# ZynqCoreBoard1.net
KiCad netlist of a schematic drawn in Altium Designer
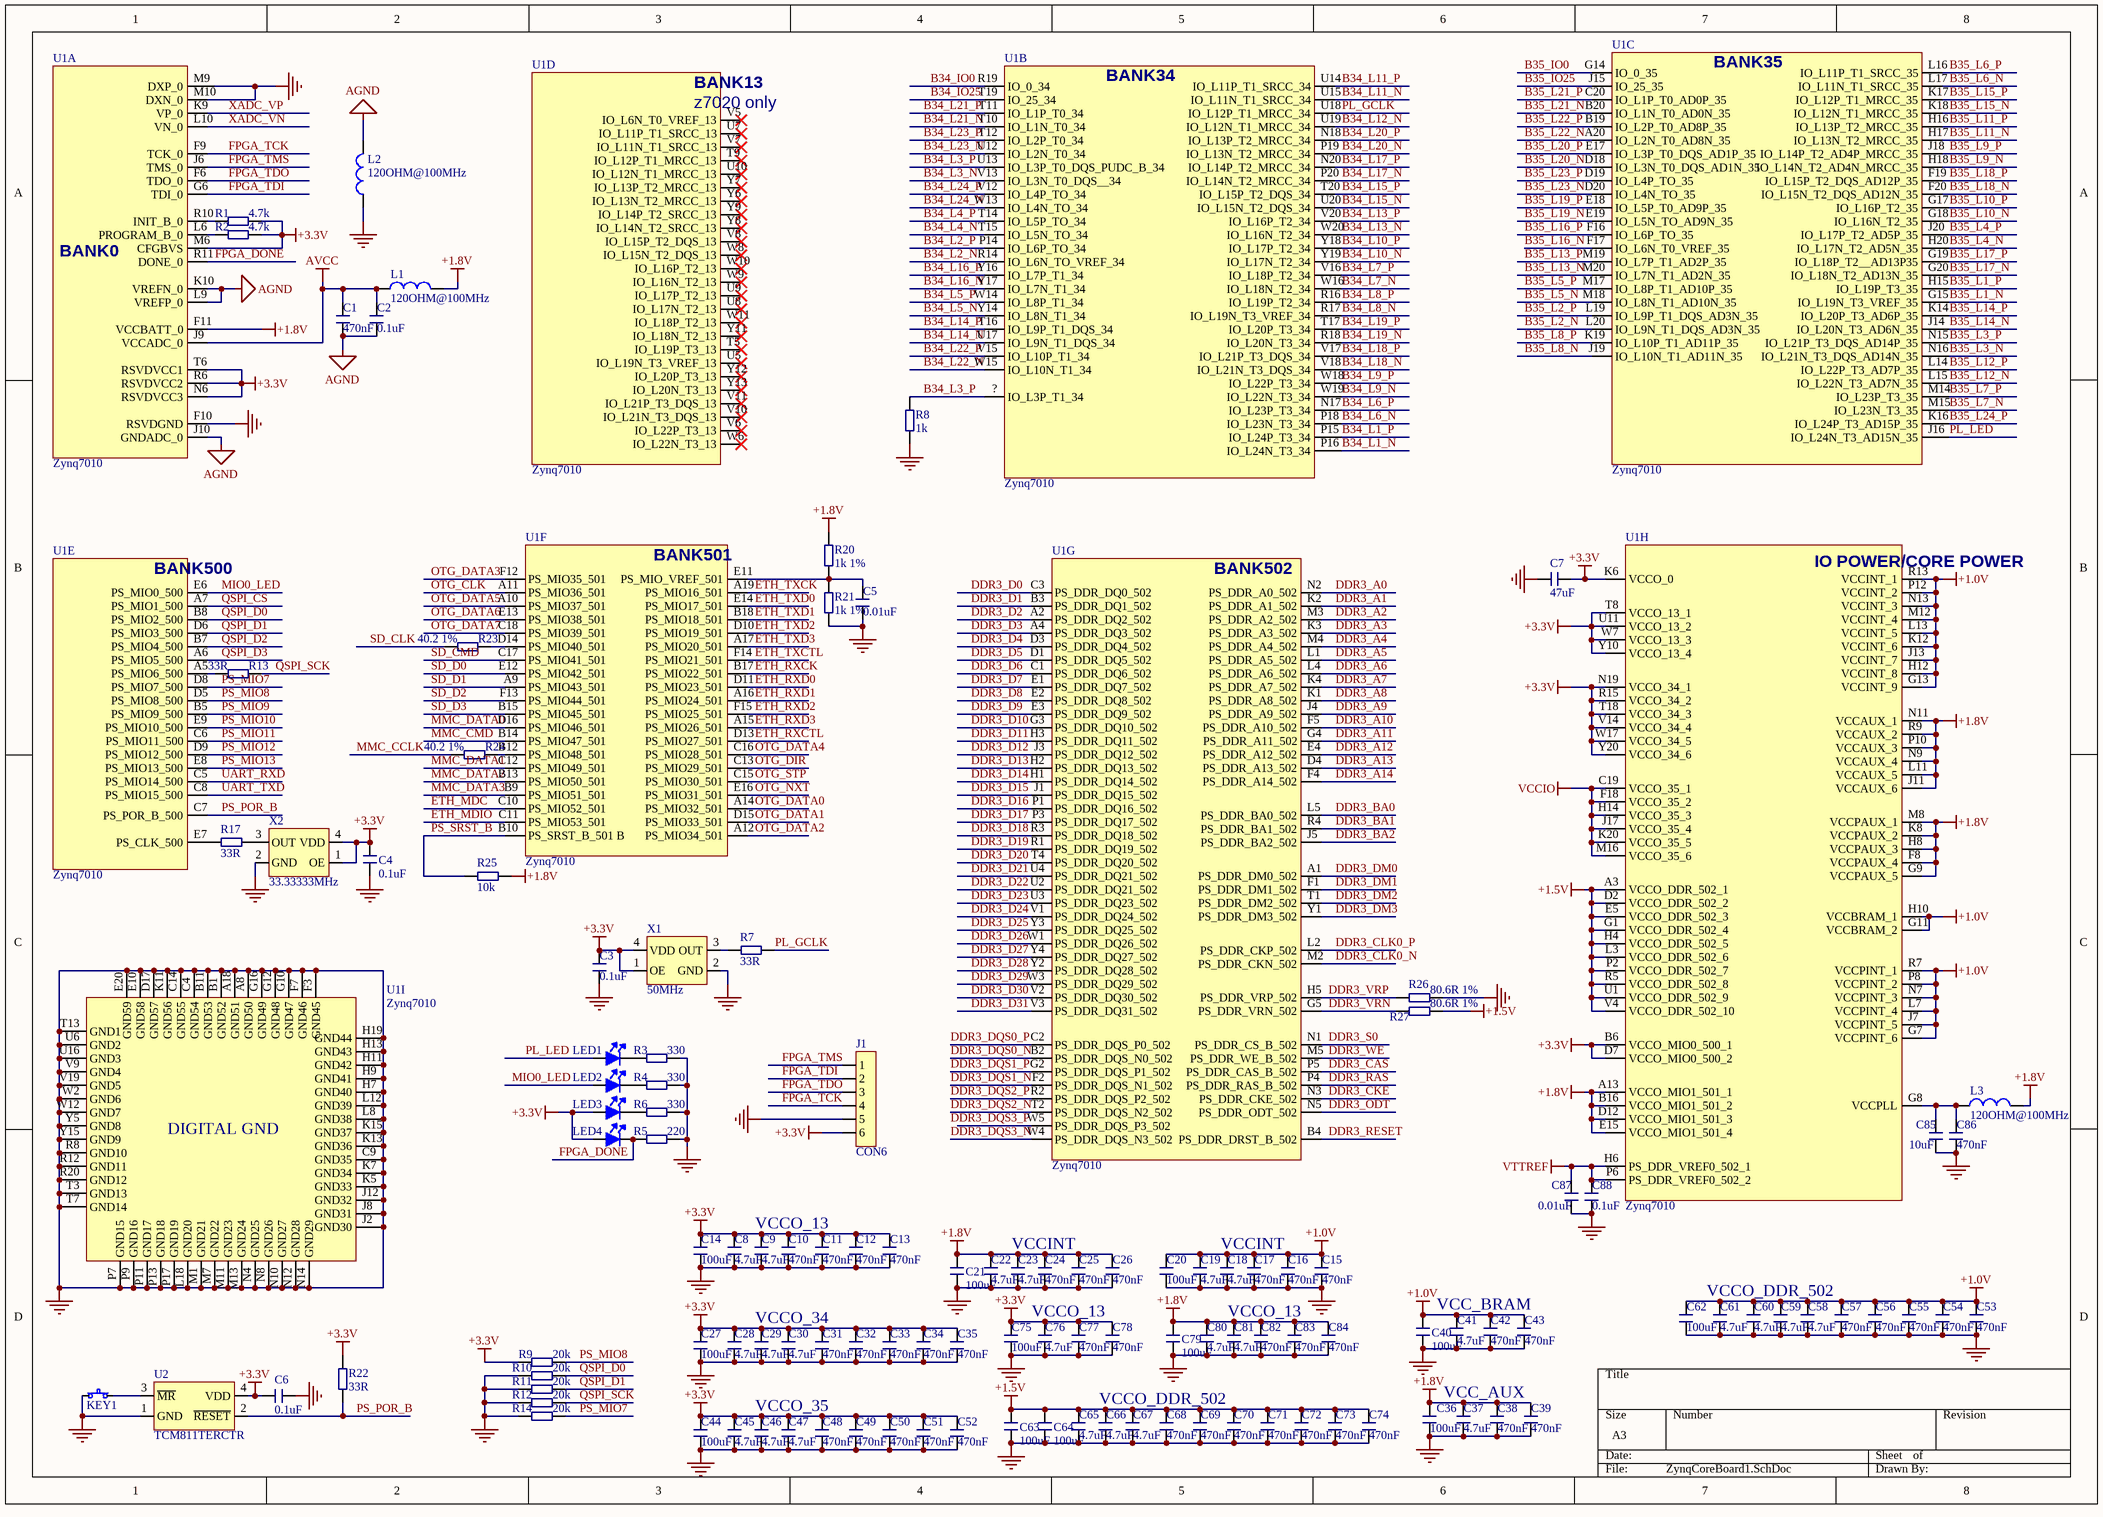
[diagram p0: ZynqCoreBoard1.SchDoc]

(export (version "E")
  (design (tool "Eeschema 10.0.6"))
  (components
    (comp (ref "C1")
      (value "470nF")
      (footprint "C0402")
      (libsource (lib "zynqCoreboard_SCHLIB") (part "C0402"))
    )
    (comp (ref "C2")
      (value "0.1uF")
      (footprint "C0402")
      (libsource (lib "zynqCoreboard_SCHLIB") (part "C0402"))
    )
    (comp (ref "C3")
      (value "0.1uF")
      (footprint "C0402")
      (libsource (lib "zynqCoreboard_SCHLIB") (part "C0402"))
    )
    (comp (ref "C4")
      (value "0.1uF")
      (footprint "C0402")
      (libsource (lib "zynqCoreboard_SCHLIB") (part "C0402"))
    )
    (comp (ref "C5")
      (value "0.01uF")
      (footprint "C0402")
      (libsource (lib "zynqCoreboard_SCHLIB") (part "C0402"))
    )
    (comp (ref "C6")
      (value "0.1uF")
      (footprint "C0402")
      (libsource (lib "zynqCoreboard_SCHLIB") (part "C0402"))
    )
    (comp (ref "C7")
      (value "47uF")
      (footprint "C0603")
      (libsource (lib "zynqCoreboard_SCHLIB") (part "C0603"))
    )
    (comp (ref "C8")
      (value "4.7uF")
      (footprint "C0402")
      (libsource (lib "zynqCoreboard_SCHLIB") (part "C0402"))
    )
    (comp (ref "C9")
      (value "4.7uF")
      (footprint "C0402")
      (libsource (lib "zynqCoreboard_SCHLIB") (part "C0402"))
    )
    (comp (ref "C10")
      (value "470nF")
      (footprint "C0402")
      (libsource (lib "zynqCoreboard_SCHLIB") (part "C0402"))
    )
    (comp (ref "C11")
      (value "470nF")
      (footprint "C0402")
      (libsource (lib "zynqCoreboard_SCHLIB") (part "C0402"))
    )
    (comp (ref "C12")
      (value "470nF")
      (footprint "C0402")
      (libsource (lib "zynqCoreboard_SCHLIB") (part "C0402"))
    )
    (comp (ref "C13")
      (value "470nF")
      (footprint "C0402")
      (libsource (lib "zynqCoreboard_SCHLIB") (part "C0402"))
    )
    (comp (ref "C14")
      (value "100uF")
      (footprint "C1206")
      (libsource (lib "zynqCoreboard_SCHLIB") (part "C_3528B"))
    )
    (comp (ref "C15")
      (value "470nF")
      (footprint "C0402")
      (libsource (lib "zynqCoreboard_SCHLIB") (part "C0402"))
    )
    (comp (ref "C16")
      (value "470nF")
      (footprint "C0402")
      (libsource (lib "zynqCoreboard_SCHLIB") (part "C0402"))
    )
    (comp (ref "C17")
      (value "470nF")
      (footprint "C0402")
      (libsource (lib "zynqCoreboard_SCHLIB") (part "C0402"))
    )
    (comp (ref "C18")
      (value "4.7uF")
      (footprint "C0402")
      (libsource (lib "zynqCoreboard_SCHLIB") (part "C0402"))
    )
    (comp (ref "C19")
      (value "4.7uF")
      (footprint "C0402")
      (libsource (lib "zynqCoreboard_SCHLIB") (part "C0402"))
    )
    (comp (ref "C20")
      (value "100uF")
      (footprint "C1206")
      (libsource (lib "zynqCoreboard_SCHLIB") (part "C_3528B"))
    )
    (comp (ref "C21")
      (value "100uF")
      (footprint "C1206")
      (libsource (lib "zynqCoreboard_SCHLIB") (part "C_3528B"))
    )
    (comp (ref "C22")
      (value "4.7uF")
      (footprint "C0402")
      (libsource (lib "zynqCoreboard_SCHLIB") (part "C0402"))
    )
    (comp (ref "C23")
      (value "4.7uF")
      (footprint "C0402")
      (libsource (lib "zynqCoreboard_SCHLIB") (part "C0402"))
    )
    (comp (ref "C24")
      (value "470nF")
      (footprint "C0402")
      (libsource (lib "zynqCoreboard_SCHLIB") (part "C0402"))
    )
    (comp (ref "C25")
      (value "470nF")
      (footprint "C0402")
      (libsource (lib "zynqCoreboard_SCHLIB") (part "C0402"))
    )
    (comp (ref "C26")
      (value "470nF")
      (footprint "C0402")
      (libsource (lib "zynqCoreboard_SCHLIB") (part "C0402"))
    )
    (comp (ref "C27")
      (value "100uF")
      (footprint "C1206")
      (libsource (lib "zynqCoreboard_SCHLIB") (part "C_3528B"))
    )
    (comp (ref "C28")
      (value "4.7uF")
      (footprint "C0402")
      (libsource (lib "zynqCoreboard_SCHLIB") (part "C0402"))
    )
    (comp (ref "C29")
      (value "4.7uF")
      (footprint "C0402")
      (libsource (lib "zynqCoreboard_SCHLIB") (part "C0402"))
    )
    (comp (ref "C30")
      (value "4.7uF")
      (footprint "C0402")
      (libsource (lib "zynqCoreboard_SCHLIB") (part "C0402"))
    )
    (comp (ref "C31")
      (value "470nF")
      (footprint "C0402")
      (libsource (lib "zynqCoreboard_SCHLIB") (part "C0402"))
    )
    (comp (ref "C32")
      (value "470nF")
      (footprint "C0402")
      (libsource (lib "zynqCoreboard_SCHLIB") (part "C0402"))
    )
    (comp (ref "C33")
      (value "470nF")
      (footprint "C0402")
      (libsource (lib "zynqCoreboard_SCHLIB") (part "C0402"))
    )
    (comp (ref "C34")
      (value "470nF")
      (footprint "C0402")
      (libsource (lib "zynqCoreboard_SCHLIB") (part "C0402"))
    )
    (comp (ref "C35")
      (value "470nF")
      (footprint "C0402")
      (libsource (lib "zynqCoreboard_SCHLIB") (part "C0402"))
    )
    (comp (ref "C36")
      (value "100uF")
      (footprint "C1206")
      (libsource (lib "zynqCoreboard_SCHLIB") (part "C_3528B"))
    )
    (comp (ref "C37")
      (value "4.7uF")
      (footprint "C0402")
      (libsource (lib "zynqCoreboard_SCHLIB") (part "C0402"))
    )
    (comp (ref "C38")
      (value "470nF")
      (footprint "C0402")
      (libsource (lib "zynqCoreboard_SCHLIB") (part "C0402"))
    )
    (comp (ref "C39")
      (value "470nF")
      (footprint "C0402")
      (libsource (lib "zynqCoreboard_SCHLIB") (part "C0402"))
    )
    (comp (ref "C40")
      (value "100uF")
      (footprint "C0603")
      (libsource (lib "zynqCoreboard_SCHLIB") (part "C0603"))
    )
    (comp (ref "C41")
      (value "4.7uF")
      (footprint "C0402")
      (libsource (lib "zynqCoreboard_SCHLIB") (part "C0402"))
    )
    (comp (ref "C42")
      (value "470nF")
      (footprint "C0402")
      (libsource (lib "zynqCoreboard_SCHLIB") (part "C0402"))
    )
    (comp (ref "C43")
      (value "470nF")
      (footprint "C0402")
      (libsource (lib "zynqCoreboard_SCHLIB") (part "C0402"))
    )
    (comp (ref "C44")
      (value "100uF")
      (footprint "C1206")
      (libsource (lib "zynqCoreboard_SCHLIB") (part "C_3528B"))
    )
    (comp (ref "C45")
      (value "4.7uF")
      (footprint "C0402")
      (libsource (lib "zynqCoreboard_SCHLIB") (part "C0402"))
    )
    (comp (ref "C46")
      (value "4.7uF")
      (footprint "C0402")
      (libsource (lib "zynqCoreboard_SCHLIB") (part "C0402"))
    )
    (comp (ref "C47")
      (value "4.7uF")
      (footprint "C0402")
      (libsource (lib "zynqCoreboard_SCHLIB") (part "C0402"))
    )
    (comp (ref "C48")
      (value "470nF")
      (footprint "C0402")
      (libsource (lib "zynqCoreboard_SCHLIB") (part "C0402"))
    )
    (comp (ref "C49")
      (value "470nF")
      (footprint "C0402")
      (libsource (lib "zynqCoreboard_SCHLIB") (part "C0402"))
    )
    (comp (ref "C50")
      (value "470nF")
      (footprint "C0402")
      (libsource (lib "zynqCoreboard_SCHLIB") (part "C0402"))
    )
    (comp (ref "C51")
      (value "470nF")
      (footprint "C0402")
      (libsource (lib "zynqCoreboard_SCHLIB") (part "C0402"))
    )
    (comp (ref "C52")
      (value "470nF")
      (footprint "C0402")
      (libsource (lib "zynqCoreboard_SCHLIB") (part "C0402"))
    )
    (comp (ref "C53")
      (value "470nF")
      (footprint "C0402")
      (libsource (lib "zynqCoreboard_SCHLIB") (part "C0402"))
    )
    (comp (ref "C54")
      (value "470nF")
      (footprint "C0402")
      (libsource (lib "zynqCoreboard_SCHLIB") (part "C0402"))
    )
    (comp (ref "C55")
      (value "470nF")
      (footprint "C0402")
      (libsource (lib "zynqCoreboard_SCHLIB") (part "C0402"))
    )
    (comp (ref "C56")
      (value "470nF")
      (footprint "C0402")
      (libsource (lib "zynqCoreboard_SCHLIB") (part "C0402"))
    )
    (comp (ref "C57")
      (value "470nF")
      (footprint "C0402")
      (libsource (lib "zynqCoreboard_SCHLIB") (part "C0402"))
    )
    (comp (ref "C58")
      (value "4.7uF")
      (footprint "C0402")
      (libsource (lib "zynqCoreboard_SCHLIB") (part "C0402"))
    )
    (comp (ref "C59")
      (value "4.7uF")
      (footprint "C0402")
      (libsource (lib "zynqCoreboard_SCHLIB") (part "C0402"))
    )
    (comp (ref "C60")
      (value "4.7uF")
      (footprint "C0402")
      (libsource (lib "zynqCoreboard_SCHLIB") (part "C0402"))
    )
    (comp (ref "C61")
      (value "4.7uF")
      (footprint "C0402")
      (libsource (lib "zynqCoreboard_SCHLIB") (part "C0402"))
    )
    (comp (ref "C62")
      (value "100uF")
      (footprint "C1206")
      (libsource (lib "zynqCoreboard_SCHLIB") (part "C_3528B"))
    )
    (comp (ref "C63")
      (value "100uF")
      (footprint "C1206")
      (libsource (lib "zynqCoreboard_SCHLIB") (part "C_3528B"))
    )
    (comp (ref "C64")
      (value "100uF")
      (footprint "C1206")
      (libsource (lib "zynqCoreboard_SCHLIB") (part "C_3528B"))
    )
    (comp (ref "C65")
      (value "4.7uF")
      (footprint "C0402")
      (libsource (lib "zynqCoreboard_SCHLIB") (part "C0402"))
    )
    (comp (ref "C66")
      (value "4.7uF")
      (footprint "C0402")
      (libsource (lib "zynqCoreboard_SCHLIB") (part "C0402"))
    )
    (comp (ref "C67")
      (value "4.7uF")
      (footprint "C0402")
      (libsource (lib "zynqCoreboard_SCHLIB") (part "C0402"))
    )
    (comp (ref "C68")
      (value "470nF")
      (footprint "C0402")
      (libsource (lib "zynqCoreboard_SCHLIB") (part "C0402"))
    )
    (comp (ref "C69")
      (value "470nF")
      (footprint "C0402")
      (libsource (lib "zynqCoreboard_SCHLIB") (part "C0402"))
    )
    (comp (ref "C70")
      (value "470nF")
      (footprint "C0402")
      (libsource (lib "zynqCoreboard_SCHLIB") (part "C0402"))
    )
    (comp (ref "C71")
      (value "470nF")
      (footprint "C0402")
      (libsource (lib "zynqCoreboard_SCHLIB") (part "C0402"))
    )
    (comp (ref "C72")
      (value "470nF")
      (footprint "C0402")
      (libsource (lib "zynqCoreboard_SCHLIB") (part "C0402"))
    )
    (comp (ref "C73")
      (value "470nF")
      (footprint "C0402")
      (libsource (lib "zynqCoreboard_SCHLIB") (part "C0402"))
    )
    (comp (ref "C74")
      (value "470nF")
      (footprint "C0402")
      (libsource (lib "zynqCoreboard_SCHLIB") (part "C0402"))
    )
    (comp (ref "C75")
      (value "100uF")
      (footprint "C1206")
      (libsource (lib "zynqCoreboard_SCHLIB") (part "C1206"))
    )
    (comp (ref "C76")
      (value "4.7uF")
      (footprint "C0402")
      (libsource (lib "zynqCoreboard_SCHLIB") (part "C0402"))
    )
    (comp (ref "C77")
      (value "470nF")
      (footprint "C0402")
      (libsource (lib "zynqCoreboard_SCHLIB") (part "C0402"))
    )
    (comp (ref "C78")
      (value "470nF")
      (footprint "C0402")
      (libsource (lib "zynqCoreboard_SCHLIB") (part "C0402"))
    )
    (comp (ref "C79")
      (value "100uF")
      (footprint "C1206")
      (libsource (lib "zynqCoreboard_SCHLIB") (part "C_3528B"))
    )
    (comp (ref "C80")
      (value "4.7uF")
      (footprint "C0402")
      (libsource (lib "zynqCoreboard_SCHLIB") (part "C0402"))
    )
    (comp (ref "C81")
      (value "4.7uF")
      (footprint "C0402")
      (libsource (lib "zynqCoreboard_SCHLIB") (part "C0402"))
    )
    (comp (ref "C82")
      (value "470nF")
      (footprint "C0402")
      (libsource (lib "zynqCoreboard_SCHLIB") (part "C0402"))
    )
    (comp (ref "C83")
      (value "470nF")
      (footprint "C0402")
      (libsource (lib "zynqCoreboard_SCHLIB") (part "C0402"))
    )
    (comp (ref "C84")
      (value "470nF")
      (footprint "C0402")
      (libsource (lib "zynqCoreboard_SCHLIB") (part "C0402"))
    )
    (comp (ref "C85")
      (value "10uF")
      (footprint "C0603")
      (libsource (lib "zynqCoreboard_SCHLIB") (part "C0603"))
    )
    (comp (ref "C86")
      (value "470nF")
      (footprint "C0402")
      (libsource (lib "zynqCoreboard_SCHLIB") (part "C0402"))
    )
    (comp (ref "C87")
      (value "0.01uF")
      (footprint "C0402")
      (libsource (lib "zynqCoreboard_SCHLIB") (part "C0402"))
    )
    (comp (ref "C88")
      (value "0.1uF")
      (footprint "C0402")
      (libsource (lib "zynqCoreboard_SCHLIB") (part "C0402"))
    )
    (comp (ref "J1")
      (value "CON6")
      (footprint "HDR2.54-LI-6P")
      (libsource (lib "zynqCoreboard_SCHLIB") (part "CON_1x6Pin_2.54"))
    )
    (comp (ref "KEY1")
      (value "Button")
      (footprint "TSW SMD-3*6*2.5")
      (libsource (lib "zynqCoreboard_SCHLIB") (part "Key"))
    )
    (comp (ref "L1")
      (value "120OHM@100MHz")
      (footprint "L0402")
      (libsource (lib "zynqCoreboard_SCHLIB") (part "L0402"))
    )
    (comp (ref "L2")
      (value "120OHM@100MHz")
      (footprint "L0402")
      (libsource (lib "zynqCoreboard_SCHLIB") (part "L0402"))
    )
    (comp (ref "L3")
      (value "120OHM@100MHz")
      (footprint "L0402")
      (libsource (lib "zynqCoreboard_SCHLIB") (part "L0402"))
    )
    (comp (ref "LED1")
      (value "LED")
      (footprint "LED 0603G")
      (libsource (lib "zynqCoreboard_SCHLIB") (part "LED_0603"))
    )
    (comp (ref "LED2")
      (value "LED")
      (footprint "LED 0603G")
      (libsource (lib "zynqCoreboard_SCHLIB") (part "LED_0603"))
    )
    (comp (ref "LED3")
      (value "LED")
      (footprint "LED 0603G")
      (libsource (lib "zynqCoreboard_SCHLIB") (part "LED_0603"))
    )
    (comp (ref "LED4")
      (value "LED")
      (footprint "LED 0603G")
      (libsource (lib "zynqCoreboard_SCHLIB") (part "LED_0603"))
    )
    (comp (ref "R1")
      (value "4.7k")
      (footprint "R0402")
      (libsource (lib "zynqCoreboard_SCHLIB") (part "R0402"))
    )
    (comp (ref "R2")
      (value "4.7k")
      (footprint "R0402")
      (libsource (lib "zynqCoreboard_SCHLIB") (part "R0402"))
    )
    (comp (ref "R3")
      (value "330")
      (footprint "R0402")
      (libsource (lib "zynqCoreboard_SCHLIB") (part "R0402"))
    )
    (comp (ref "R4")
      (value "330")
      (footprint "R0402")
      (libsource (lib "zynqCoreboard_SCHLIB") (part "R0402"))
    )
    (comp (ref "R5")
      (value "220")
      (footprint "R0402")
      (libsource (lib "zynqCoreboard_SCHLIB") (part "R0402"))
    )
    (comp (ref "R6")
      (value "330")
      (footprint "R0402")
      (libsource (lib "zynqCoreboard_SCHLIB") (part "R0402"))
    )
    (comp (ref "R7")
      (value "33R")
      (footprint "R0402")
      (libsource (lib "zynqCoreboard_SCHLIB") (part "R0402"))
    )
    (comp (ref "R8") (value "1k") (footprint "R0402") (libsource (lib "zynqCoreboard_SCHLIB") (part "R0402")))
    (comp (ref "R9")
      (value "20k")
      (footprint "R0402")
      (libsource (lib "zynqCoreboard_SCHLIB") (part "R0402"))
    )
    (comp (ref "R10")
      (value "20k")
      (footprint "R0402")
      (libsource (lib "zynqCoreboard_SCHLIB") (part "R0402"))
    )
    (comp (ref "R11")
      (value "20k")
      (footprint "R0402")
      (libsource (lib "zynqCoreboard_SCHLIB") (part "R0402"))
    )
    (comp (ref "R12")
      (value "20k")
      (footprint "R0402")
      (libsource (lib "zynqCoreboard_SCHLIB") (part "R0402"))
    )
    (comp (ref "R13")
      (value "33R")
      (footprint "R0402")
      (libsource (lib "zynqCoreboard_SCHLIB") (part "R0402"))
    )
    (comp (ref "R14")
      (value "20k")
      (footprint "R0402")
      (libsource (lib "zynqCoreboard_SCHLIB") (part "R0402"))
    )
    (comp (ref "R17")
      (value "33R")
      (footprint "R0402")
      (libsource (lib "zynqCoreboard_SCHLIB") (part "R0402"))
    )
    (comp (ref "R20")
      (value "1k 1%")
      (footprint "R0402")
      (libsource (lib "zynqCoreboard_SCHLIB") (part "R0402"))
    )
    (comp (ref "R21")
      (value "1k 1%")
      (footprint "R0402")
      (libsource (lib "zynqCoreboard_SCHLIB") (part "R0402"))
    )
    (comp (ref "R22")
      (value "33R")
      (footprint "R0402")
      (libsource (lib "zynqCoreboard_SCHLIB") (part "R0402"))
    )
    (comp (ref "R23")
      (value "40.2 1%")
      (footprint "R0402")
      (libsource (lib "zynqCoreboard_SCHLIB") (part "R0402"))
    )
    (comp (ref "R24")
      (value "40.2 1%")
      (footprint "R0402")
      (libsource (lib "zynqCoreboard_SCHLIB") (part "R0402"))
    )
    (comp (ref "R25")
      (value "10k")
      (footprint "R0402")
      (libsource (lib "zynqCoreboard_SCHLIB") (part "R0402"))
    )
    (comp (ref "R26")
      (value "80.6R 1%")
      (footprint "R0402")
      (libsource (lib "zynqCoreboard_SCHLIB") (part "R0402"))
    )
    (comp (ref "R27")
      (value "80.6R 1%")
      (footprint "R0402")
      (libsource (lib "zynqCoreboard_SCHLIB") (part "R0402"))
    )
    (comp (ref "U1")
      (value "Zynq7010")
      (footprint "zynq7020CL400")
      (libsource (lib "zynqCoreboard_SCHLIB") (part "Zynq7010"))
    )
    (comp (ref "U2")
      (value "TCM811TERCTR")
      (footprint "SOT143")
      (libsource (lib "zynqCoreboard_SCHLIB") (part "TCM811TERCTR"))
    )
    (comp (ref "X1")
      (value "50MHz")
      (footprint "OSC 3225-4P")
      (libsource (lib "zynqCoreboard_SCHLIB") (part "XTAL_50MHz_3225"))
    )
    (comp (ref "X2")
      (value "33.33333MHz")
      (footprint "OSC 3225-4P")
      (libsource (lib "") (part "XTAL_50MHz_3225_1"))
    )
  )
  (nets
    (net (code "1") (name "+1.0V") (class "Default")
      (node (ref "C15") (pin "2") (pinfunction "2_2") (pintype "passive"))
      (node (ref "C16") (pin "2") (pinfunction "2_2") (pintype "passive"))
      (node (ref "C17") (pin "2") (pinfunction "2_2") (pintype "passive"))
      (node (ref "C18") (pin "2") (pinfunction "2_2") (pintype "passive"))
      (node (ref "C19") (pin "2") (pinfunction "2_2") (pintype "passive"))
      (node (ref "C20") (pin "2") (pinfunction "2_2") (pintype "passive"))
      (node (ref "C40") (pin "2") (pinfunction "2_2") (pintype "passive"))
      (node (ref "C41") (pin "2") (pinfunction "2_2") (pintype "passive"))
      (node (ref "C42") (pin "2") (pinfunction "2_2") (pintype "passive"))
      (node (ref "C43") (pin "2") (pinfunction "2_2") (pintype "passive"))
      (node (ref "C53") (pin "2") (pinfunction "2_2") (pintype "passive"))
      (node (ref "C54") (pin "2") (pinfunction "2_2") (pintype "passive"))
      (node (ref "C55") (pin "2") (pinfunction "2_2") (pintype "passive"))
      (node (ref "C56") (pin "2") (pinfunction "2_2") (pintype "passive"))
      (node (ref "C57") (pin "2") (pinfunction "2_2") (pintype "passive"))
      (node (ref "C58") (pin "2") (pinfunction "2_2") (pintype "passive"))
      (node (ref "C59") (pin "2") (pinfunction "2_2") (pintype "passive"))
      (node (ref "C60") (pin "2") (pinfunction "2_2") (pintype "passive"))
      (node (ref "C61") (pin "2") (pinfunction "2_2") (pintype "passive"))
      (node (ref "C62") (pin "2") (pinfunction "2_2") (pintype "passive"))
      (node (ref "U1") (pin "G11") (pinfunction "VCCBRAM_2_G11") (pintype "passive"))
      (node (ref "U1") (pin "G13") (pinfunction "VCCINT_9_G13") (pintype "passive"))
      (node (ref "U1") (pin "G7") (pinfunction "VCCPINT_6_G7") (pintype "passive"))
      (node (ref "U1") (pin "H10") (pinfunction "VCCBRAM_1_H10") (pintype "passive"))
      (node (ref "U1") (pin "H12") (pinfunction "VCCINT_8_H12") (pintype "passive"))
      (node (ref "U1") (pin "J13") (pinfunction "VCCINT_7_J13") (pintype "passive"))
      (node (ref "U1") (pin "J7") (pinfunction "VCCPINT_5_J7") (pintype "passive"))
      (node (ref "U1") (pin "K12") (pinfunction "VCCINT_6_K12") (pintype "passive"))
      (node (ref "U1") (pin "L13") (pinfunction "VCCINT_5_L13") (pintype "passive"))
      (node (ref "U1") (pin "L7") (pinfunction "VCCPINT_4_L7") (pintype "passive"))
      (node (ref "U1") (pin "M12") (pinfunction "VCCINT_4_M12") (pintype "passive"))
      (node (ref "U1") (pin "N13") (pinfunction "VCCINT_3_N13") (pintype "passive"))
      (node (ref "U1") (pin "N7") (pinfunction "VCCPINT_3_N7") (pintype "passive"))
      (node (ref "U1") (pin "P12") (pinfunction "VCCINT_2_P12") (pintype "passive"))
      (node (ref "U1") (pin "P8") (pinfunction "VCCPINT_2_P8") (pintype "passive"))
      (node (ref "U1") (pin "R13") (pinfunction "VCCINT_1_R13") (pintype "passive"))
      (node (ref "U1") (pin "R7") (pinfunction "VCCPINT_1_R7") (pintype "passive"))
    )
    (net (code "2") (name "+1.5V") (class "Default")
      (node (ref "C63") (pin "2") (pinfunction "2_2") (pintype "passive"))
      (node (ref "C64") (pin "2") (pinfunction "2_2") (pintype "passive"))
      (node (ref "C65") (pin "2") (pinfunction "2_2") (pintype "passive"))
      (node (ref "C66") (pin "2") (pinfunction "2_2") (pintype "passive"))
      (node (ref "C67") (pin "2") (pinfunction "2_2") (pintype "passive"))
      (node (ref "C68") (pin "2") (pinfunction "2_2") (pintype "passive"))
      (node (ref "C69") (pin "2") (pinfunction "2_2") (pintype "passive"))
      (node (ref "C70") (pin "2") (pinfunction "2_2") (pintype "passive"))
      (node (ref "C71") (pin "2") (pinfunction "2_2") (pintype "passive"))
      (node (ref "C72") (pin "2") (pinfunction "2_2") (pintype "passive"))
      (node (ref "C73") (pin "2") (pinfunction "2_2") (pintype "passive"))
      (node (ref "C74") (pin "2") (pinfunction "2_2") (pintype "passive"))
      (node (ref "R27") (pin "2") (pinfunction "2_2") (pintype "passive"))
      (node (ref "U1") (pin "A3") (pinfunction "VCCO_DDR_502_1_A3") (pintype "passive"))
      (node (ref "U1") (pin "D2") (pinfunction "VCCO_DDR_502_2_D2") (pintype "passive"))
      (node (ref "U1") (pin "E5") (pinfunction "VCCO_DDR_502_3_E5") (pintype "passive"))
      (node (ref "U1") (pin "G1") (pinfunction "VCCO_DDR_502_4_G1") (pintype "passive"))
      (node (ref "U1") (pin "H4") (pinfunction "VCCO_DDR_502_5_H4") (pintype "passive"))
      (node (ref "U1") (pin "L3") (pinfunction "VCCO_DDR_502_6_L3") (pintype "passive"))
      (node (ref "U1") (pin "P2") (pinfunction "VCCO_DDR_502_7_P2") (pintype "passive"))
      (node (ref "U1") (pin "R5") (pinfunction "VCCO_DDR_502_8_R5") (pintype "passive"))
      (node (ref "U1") (pin "U1") (pinfunction "VCCO_DDR_502_9_U1") (pintype "passive"))
      (node (ref "U1") (pin "V4") (pinfunction "VCCO_DDR_502_10_V4") (pintype "passive"))
    )
    (net (code "3") (name "+1.8V") (class "Default")
      (node (ref "C21") (pin "2") (pinfunction "2_2") (pintype "passive"))
      (node (ref "C22") (pin "2") (pinfunction "2_2") (pintype "passive"))
      (node (ref "C23") (pin "2") (pinfunction "2_2") (pintype "passive"))
      (node (ref "C24") (pin "2") (pinfunction "2_2") (pintype "passive"))
      (node (ref "C25") (pin "2") (pinfunction "2_2") (pintype "passive"))
      (node (ref "C26") (pin "2") (pinfunction "2_2") (pintype "passive"))
      (node (ref "C36") (pin "2") (pinfunction "2_2") (pintype "passive"))
      (node (ref "C37") (pin "2") (pinfunction "2_2") (pintype "passive"))
      (node (ref "C38") (pin "2") (pinfunction "2_2") (pintype "passive"))
      (node (ref "C39") (pin "2") (pinfunction "2_2") (pintype "passive"))
      (node (ref "C79") (pin "2") (pinfunction "2_2") (pintype "passive"))
      (node (ref "C80") (pin "2") (pinfunction "2_2") (pintype "passive"))
      (node (ref "C81") (pin "2") (pinfunction "2_2") (pintype "passive"))
      (node (ref "C82") (pin "2") (pinfunction "2_2") (pintype "passive"))
      (node (ref "C83") (pin "2") (pinfunction "2_2") (pintype "passive"))
      (node (ref "C84") (pin "2") (pinfunction "2_2") (pintype "passive"))
      (node (ref "L1") (pin "2") (pinfunction "2_2") (pintype "passive"))
      (node (ref "L3") (pin "2") (pinfunction "2_2") (pintype "passive"))
      (node (ref "R20") (pin "2") (pinfunction "2_2") (pintype "passive"))
      (node (ref "R25") (pin "2") (pinfunction "2_2") (pintype "passive"))
      (node (ref "U1") (pin "A13") (pinfunction "VCCO_MIO1_501_1_A13") (pintype "passive"))
      (node (ref "U1") (pin "B16") (pinfunction "VCCO_MIO1_501_2_B16") (pintype "passive"))
      (node (ref "U1") (pin "D12") (pinfunction "VCCO_MIO1_501_3_D12") (pintype "passive"))
      (node (ref "U1") (pin "E15") (pinfunction "VCCO_MIO1_501_4_E15") (pintype "passive"))
      (node (ref "U1") (pin "F11") (pinfunction "VCCBATT_0_F11") (pintype "passive"))
      (node (ref "U1") (pin "F8") (pinfunction "VCCPAUX_4_F8") (pintype "passive"))
      (node (ref "U1") (pin "G9") (pinfunction "VCCPAUX_5_G9") (pintype "passive"))
      (node (ref "U1") (pin "H8") (pinfunction "VCCPAUX_3_H8") (pintype "passive"))
      (node (ref "U1") (pin "J11") (pinfunction "VCCAUX_6_J11") (pintype "passive"))
      (node (ref "U1") (pin "K8") (pinfunction "VCCPAUX_2_K8") (pintype "passive"))
      (node (ref "U1") (pin "L11") (pinfunction "VCCAUX_5_L11") (pintype "passive"))
      (node (ref "U1") (pin "M8") (pinfunction "VCCPAUX_1_M8") (pintype "passive"))
      (node (ref "U1") (pin "N11") (pinfunction "VCCAUX_1_N11") (pintype "passive"))
      (node (ref "U1") (pin "N9") (pinfunction "VCCAUX_4_N9") (pintype "passive"))
      (node (ref "U1") (pin "P10") (pinfunction "VCCAUX_3_P10") (pintype "passive"))
      (node (ref "U1") (pin "R9") (pinfunction "VCCAUX_2_R9") (pintype "passive"))
    )
    (net (code "4") (name "+3.3V") (class "Default")
      (node (ref "C10") (pin "2") (pinfunction "2_2") (pintype "passive"))
      (node (ref "C11") (pin "2") (pinfunction "2_2") (pintype "passive"))
      (node (ref "C12") (pin "2") (pinfunction "2_2") (pintype "passive"))
      (node (ref "C13") (pin "2") (pinfunction "2_2") (pintype "passive"))
      (node (ref "C14") (pin "2") (pinfunction "2_2") (pintype "passive"))
      (node (ref "C27") (pin "2") (pinfunction "2_2") (pintype "passive"))
      (node (ref "C28") (pin "2") (pinfunction "2_2") (pintype "passive"))
      (node (ref "C29") (pin "2") (pinfunction "2_2") (pintype "passive"))
      (node (ref "C3") (pin "2") (pinfunction "2_2") (pintype "passive"))
      (node (ref "C30") (pin "2") (pinfunction "2_2") (pintype "passive"))
      (node (ref "C31") (pin "2") (pinfunction "2_2") (pintype "passive"))
      (node (ref "C32") (pin "2") (pinfunction "2_2") (pintype "passive"))
      (node (ref "C33") (pin "2") (pinfunction "2_2") (pintype "passive"))
      (node (ref "C34") (pin "2") (pinfunction "2_2") (pintype "passive"))
      (node (ref "C35") (pin "2") (pinfunction "2_2") (pintype "passive"))
      (node (ref "C4") (pin "1") (pinfunction "1_1") (pintype "passive"))
      (node (ref "C44") (pin "2") (pinfunction "2_2") (pintype "passive"))
      (node (ref "C45") (pin "2") (pinfunction "2_2") (pintype "passive"))
      (node (ref "C46") (pin "2") (pinfunction "2_2") (pintype "passive"))
      (node (ref "C47") (pin "2") (pinfunction "2_2") (pintype "passive"))
      (node (ref "C48") (pin "2") (pinfunction "2_2") (pintype "passive"))
      (node (ref "C49") (pin "2") (pinfunction "2_2") (pintype "passive"))
      (node (ref "C50") (pin "2") (pinfunction "2_2") (pintype "passive"))
      (node (ref "C51") (pin "2") (pinfunction "2_2") (pintype "passive"))
      (node (ref "C52") (pin "2") (pinfunction "2_2") (pintype "passive"))
      (node (ref "C6") (pin "1") (pinfunction "1_1") (pintype "passive"))
      (node (ref "C7") (pin "2") (pinfunction "2_2") (pintype "passive"))
      (node (ref "C75") (pin "2") (pinfunction "2_2") (pintype "passive"))
      (node (ref "C76") (pin "2") (pinfunction "2_2") (pintype "passive"))
      (node (ref "C77") (pin "2") (pinfunction "2_2") (pintype "passive"))
      (node (ref "C78") (pin "2") (pinfunction "2_2") (pintype "passive"))
      (node (ref "C8") (pin "2") (pinfunction "2_2") (pintype "passive"))
      (node (ref "C9") (pin "2") (pinfunction "2_2") (pintype "passive"))
      (node (ref "J1") (pin "6") (pinfunction "6_6") (pintype "passive"))
      (node (ref "LED3") (pin "1") (pinfunction "1_1") (pintype "passive"))
      (node (ref "LED4") (pin "1") (pinfunction "1_1") (pintype "passive"))
      (node (ref "R1") (pin "2") (pinfunction "2_2") (pintype "passive"))
      (node (ref "R2") (pin "2") (pinfunction "2_2") (pintype "passive"))
      (node (ref "R22") (pin "2") (pinfunction "2_2") (pintype "passive"))
      (node (ref "R9") (pin "1") (pinfunction "1_1") (pintype "passive"))
      (node (ref "U1") (pin "B6") (pinfunction "VCCO_MIO0_500_1_B6") (pintype "passive"))
      (node (ref "U1") (pin "D7") (pinfunction "VCCO_MIO0_500_2_D7") (pintype "passive"))
      (node (ref "U1") (pin "K6") (pinfunction "VCCO_0_K6") (pintype "passive"))
      (node (ref "U1") (pin "M6") (pinfunction "CFGBVS_M6") (pintype "passive"))
      (node (ref "U1") (pin "N19") (pinfunction "VCCO_34_1_N19") (pintype "passive"))
      (node (ref "U1") (pin "N6") (pinfunction "RSVDVCC3_N6") (pintype "passive"))
      (node (ref "U1") (pin "R15") (pinfunction "VCCO_34_2_R15") (pintype "passive"))
      (node (ref "U1") (pin "R6") (pinfunction "RSVDVCC2_R6") (pintype "passive"))
      (node (ref "U1") (pin "T18") (pinfunction "VCCO_34_3_T18") (pintype "passive"))
      (node (ref "U1") (pin "T6") (pinfunction "RSVDVCC1_T6") (pintype "passive"))
      (node (ref "U1") (pin "T8") (pinfunction "VCCO_13_1_T8") (pintype "passive"))
      (node (ref "U1") (pin "U11") (pinfunction "VCCO_13_2_U11") (pintype "passive"))
      (node (ref "U1") (pin "V14") (pinfunction "VCCO_34_4_V14") (pintype "passive"))
      (node (ref "U1") (pin "W17") (pinfunction "VCCO_34_5_W17") (pintype "passive"))
      (node (ref "U1") (pin "W7") (pinfunction "VCCO_13_3_W7") (pintype "passive"))
      (node (ref "U1") (pin "Y10") (pinfunction "VCCO_13_4_Y10") (pintype "passive"))
      (node (ref "U1") (pin "Y20") (pinfunction "VCCO_34_6_Y20") (pintype "passive"))
      (node (ref "U2") (pin "4") (pinfunction "VDD_4") (pintype "passive"))
      (node (ref "X1") (pin "1") (pinfunction "OE_1") (pintype "passive"))
      (node (ref "X1") (pin "4") (pinfunction "VDD_4") (pintype "passive"))
      (node (ref "X2") (pin "1") (pinfunction "OE_1") (pintype "passive"))
      (node (ref "X2") (pin "4") (pinfunction "VDD_4") (pintype "passive"))
    )
    (net (code "5") (name "/B34_IO0") (class "Default")
      (node (ref "U1") (pin "R19") (pinfunction "IO_0_34_R19") (pintype "passive"))
    )
    (net (code "6") (name "/B34_IO25") (class "Default")
      (node (ref "U1") (pin "T19") (pinfunction "IO_25_34_T19") (pintype "passive"))
    )
    (net (code "7") (name "/B34_L1_N") (class "Default")
      (node (ref "U1") (pin "P16") (pinfunction "IO_L24N_T3_34_P16") (pintype "passive"))
    )
    (net (code "8") (name "/B34_L1_P") (class "Default")
      (node (ref "U1") (pin "P15") (pinfunction "IO_L24P_T3_34_P15") (pintype "passive"))
    )
    (net (code "9") (name "/B34_L2_N") (class "Default")
      (node (ref "U1") (pin "R14") (pinfunction "IO_L6N_TO_VREF_34_R14") (pintype "passive"))
    )
    (net (code "10") (name "/B34_L2_P") (class "Default")
      (node (ref "U1") (pin "P14") (pinfunction "IO_L6P_TO_34_P14") (pintype "passive"))
    )
    (net (code "11") (name "/B34_L3_N") (class "Default")
      (node (ref "U1") (pin "V13") (pinfunction "IO_L3N_T0_DQS__34_V13") (pintype "passive"))
    )
    (net (code "12") (name "/B34_L3_P") (class "Default")
      (node (ref "R8") (pin "2") (pinfunction "2_2") (pintype "passive"))
      (node (ref "U1") (pin "?") (pinfunction "IO_L3P_T1_34_?") (pintype "passive"))
      (node (ref "U1") (pin "U13") (pinfunction "IO_L3P_T0_DQS_PUDC_B_34_U13") (pintype "passive"))
    )
    (net (code "13") (name "/B34_L4_N") (class "Default")
      (node (ref "U1") (pin "T15") (pinfunction "IO_L5N_TO_34_T15") (pintype "passive"))
    )
    (net (code "14") (name "/B34_L4_P") (class "Default")
      (node (ref "U1") (pin "T14") (pinfunction "IO_L5P_TO_34_T14") (pintype "passive"))
    )
    (net (code "15") (name "/B34_L5_N") (class "Default")
      (node (ref "U1") (pin "Y14") (pinfunction "IO_L8N_T1_34_Y14") (pintype "passive"))
    )
    (net (code "16") (name "/B34_L5_P") (class "Default")
      (node (ref "U1") (pin "W14") (pinfunction "IO_L8P_T1_34_W14") (pintype "passive"))
    )
    (net (code "17") (name "/B34_L6_N") (class "Default")
      (node (ref "U1") (pin "P18") (pinfunction "IO_L23N_T3_34_P18") (pintype "passive"))
    )
    (net (code "18") (name "/B34_L6_P") (class "Default")
      (node (ref "U1") (pin "N17") (pinfunction "IO_L23P_T3_34_N17") (pintype "passive"))
    )
    (net (code "19") (name "/B34_L7_N") (class "Default")
      (node (ref "U1") (pin "W16") (pinfunction "IO_L18N_T2_34_W16") (pintype "passive"))
    )
    (net (code "20") (name "/B34_L7_P") (class "Default")
      (node (ref "U1") (pin "V16") (pinfunction "IO_L18P_T2_34_V16") (pintype "passive"))
    )
    (net (code "21") (name "/B34_L8_N") (class "Default")
      (node (ref "U1") (pin "R17") (pinfunction "IO_L19N_T3_VREF_34_R17") (pintype "passive"))
    )
    (net (code "22") (name "/B34_L8_P") (class "Default")
      (node (ref "U1") (pin "R16") (pinfunction "IO_L19P_T2_34_R16") (pintype "passive"))
    )
    (net (code "23") (name "/B34_L9_N") (class "Default")
      (node (ref "U1") (pin "W19") (pinfunction "IO_L22N_T3_34_W19") (pintype "passive"))
    )
    (net (code "24") (name "/B34_L9_P") (class "Default")
      (node (ref "U1") (pin "W18") (pinfunction "IO_L22P_T3_34_W18") (pintype "passive"))
    )
    (net (code "25") (name "/B34_L10_N") (class "Default")
      (node (ref "U1") (pin "Y19") (pinfunction "IO_L17N_T2_34_Y19") (pintype "passive"))
    )
    (net (code "26") (name "/B34_L10_P") (class "Default")
      (node (ref "U1") (pin "Y18") (pinfunction "IO_L17P_T2_34_Y18") (pintype "passive"))
    )
    (net (code "27") (name "/B34_L11_N") (class "Default")
      (node (ref "U1") (pin "U15") (pinfunction "IO_L11N_T1_SRCC_34_U15") (pintype "passive"))
    )
    (net (code "28") (name "/B34_L11_P") (class "Default")
      (node (ref "U1") (pin "U14") (pinfunction "IO_L11P_T1_SRCC_34_U14") (pintype "passive"))
    )
    (net (code "29") (name "/B34_L12_N") (class "Default")
      (node (ref "U1") (pin "U19") (pinfunction "IO_L12N_T1_MRCC_34_U19") (pintype "passive"))
    )
    (net (code "30") (name "/B34_L13_N") (class "Default")
      (node (ref "U1") (pin "W20") (pinfunction "IO_L16N_T2_34_W20") (pintype "passive"))
    )
    (net (code "31") (name "/B34_L13_P") (class "Default")
      (node (ref "U1") (pin "V20") (pinfunction "IO_L16P_T2_34_V20") (pintype "passive"))
    )
    (net (code "32") (name "/B34_L14_N") (class "Default")
      (node (ref "U1") (pin "U17") (pinfunction "IO_L9N_T1_DQS_34_U17") (pintype "passive"))
    )
    (net (code "33") (name "/B34_L14_P") (class "Default")
      (node (ref "U1") (pin "T16") (pinfunction "IO_L9P_T1_DQS_34_T16") (pintype "passive"))
    )
    (net (code "34") (name "/B34_L15_N") (class "Default")
      (node (ref "U1") (pin "U20") (pinfunction "IO_L15N_T2_DQS_34_U20") (pintype "passive"))
    )
    (net (code "35") (name "/B34_L15_P") (class "Default")
      (node (ref "U1") (pin "T20") (pinfunction "IO_L15P_T2_DQS_34_T20") (pintype "passive"))
    )
    (net (code "36") (name "/B34_L16_N") (class "Default")
      (node (ref "U1") (pin "Y17") (pinfunction "IO_L7N_T1_34_Y17") (pintype "passive"))
    )
    (net (code "37") (name "/B34_L16_P") (class "Default")
      (node (ref "U1") (pin "Y16") (pinfunction "IO_L7P_T1_34_Y16") (pintype "passive"))
    )
    (net (code "38") (name "/B34_L17_N") (class "Default")
      (node (ref "U1") (pin "P20") (pinfunction "IO_L14N_T2_MRCC_34_P20") (pintype "passive"))
    )
    (net (code "39") (name "/B34_L17_P") (class "Default")
      (node (ref "U1") (pin "N20") (pinfunction "IO_L14P_T2_MRCC_34_N20") (pintype "passive"))
    )
    (net (code "40") (name "/B34_L18_N") (class "Default")
      (node (ref "U1") (pin "V18") (pinfunction "IO_L21N_T3_DQS_34_V18") (pintype "passive"))
    )
    (net (code "41") (name "/B34_L18_P") (class "Default")
      (node (ref "U1") (pin "V17") (pinfunction "IO_L21P_T3_DQS_34_V17") (pintype "passive"))
    )
    (net (code "42") (name "/B34_L19_N") (class "Default")
      (node (ref "U1") (pin "R18") (pinfunction "IO_L20N_T3_34_R18") (pintype "passive"))
    )
    (net (code "43") (name "/B34_L19_P") (class "Default")
      (node (ref "U1") (pin "T17") (pinfunction "IO_L20P_T3_34_T17") (pintype "passive"))
    )
    (net (code "44") (name "/B34_L20_N") (class "Default")
      (node (ref "U1") (pin "P19") (pinfunction "IO_L13N_T2_MRCC_34_P19") (pintype "passive"))
    )
    (net (code "45") (name "/B34_L20_P") (class "Default")
      (node (ref "U1") (pin "N18") (pinfunction "IO_L13P_T2_MRCC_34_N18") (pintype "passive"))
    )
    (net (code "46") (name "/B34_L21_N") (class "Default")
      (node (ref "U1") (pin "T10") (pinfunction "IO_L1N_T0_34_T10") (pintype "passive"))
    )
    (net (code "47") (name "/B34_L21_P") (class "Default")
      (node (ref "U1") (pin "T11") (pinfunction "IO_L1P_T0_34_T11") (pintype "passive"))
    )
    (net (code "48") (name "/B34_L22_N") (class "Default")
      (node (ref "U1") (pin "W15") (pinfunction "IO_L10N_T1_34_W15") (pintype "passive"))
    )
    (net (code "49") (name "/B34_L22_P") (class "Default")
      (node (ref "U1") (pin "V15") (pinfunction "IO_L10P_T1_34_V15") (pintype "passive"))
    )
    (net (code "50") (name "/B34_L23_N") (class "Default")
      (node (ref "U1") (pin "U12") (pinfunction "IO_L2N_T0_34_U12") (pintype "passive"))
    )
    (net (code "51") (name "/B34_L23_P") (class "Default")
      (node (ref "U1") (pin "T12") (pinfunction "IO_L2P_T0_34_T12") (pintype "passive"))
    )
    (net (code "52") (name "/B34_L24_N") (class "Default")
      (node (ref "U1") (pin "W13") (pinfunction "IO_L4N_TO_34_W13") (pintype "passive"))
    )
    (net (code "53") (name "/B34_L24_P") (class "Default")
      (node (ref "U1") (pin "V12") (pinfunction "IO_L4P_TO_34_V12") (pintype "passive"))
    )
    (net (code "54") (name "/B35_IO0") (class "Default")
      (node (ref "U1") (pin "G14") (pinfunction "IO_0_35_G14") (pintype "passive"))
    )
    (net (code "55") (name "/B35_IO25") (class "Default")
      (node (ref "U1") (pin "J15") (pinfunction "IO_25_35_J15") (pintype "passive"))
    )
    (net (code "56") (name "/B35_L1_N") (class "Default")
      (node (ref "U1") (pin "G15") (pinfunction "IO_L19N_T3_VREF_35_G15") (pintype "passive"))
    )
    (net (code "57") (name "/B35_L1_P") (class "Default")
      (node (ref "U1") (pin "H15") (pinfunction "IO_L19P_T3_35_H15") (pintype "passive"))
    )
    (net (code "58") (name "/B35_L2_N") (class "Default")
      (node (ref "U1") (pin "L20") (pinfunction "IO_L9N_T1_DQS_AD3N_35_L20") (pintype "passive"))
    )
    (net (code "59") (name "/B35_L2_P") (class "Default")
      (node (ref "U1") (pin "L19") (pinfunction "IO_L9P_T1_DQS_AD3N_35_L19") (pintype "passive"))
    )
    (net (code "60") (name "/B35_L3_N") (class "Default")
      (node (ref "U1") (pin "N16") (pinfunction "IO_L21N_T3_DQS_AD14N_35_N16") (pintype "passive"))
    )
    (net (code "61") (name "/B35_L3_P") (class "Default")
      (node (ref "U1") (pin "N15") (pinfunction "IO_L21P_T3_DQS_AD14P_35_N15") (pintype "passive"))
    )
    (net (code "62") (name "/B35_L4_N") (class "Default")
      (node (ref "U1") (pin "H20") (pinfunction "IO_L17N_T2_AD5N_35_H20") (pintype "passive"))
    )
    (net (code "63") (name "/B35_L4_P") (class "Default")
      (node (ref "U1") (pin "J20") (pinfunction "IO_L17P_T2_AD5P_35_J20") (pintype "passive"))
    )
    (net (code "64") (name "/B35_L5_N") (class "Default")
      (node (ref "U1") (pin "M18") (pinfunction "IO_L8N_T1_AD10N_35_M18") (pintype "passive"))
    )
    (net (code "65") (name "/B35_L5_P") (class "Default")
      (node (ref "U1") (pin "M17") (pinfunction "IO_L8P_T1_AD10P_35_M17") (pintype "passive"))
    )
    (net (code "66") (name "/B35_L6_N") (class "Default")
      (node (ref "U1") (pin "L17") (pinfunction "IO_L11N_T1_SRCC_35_L17") (pintype "passive"))
    )
    (net (code "67") (name "/B35_L6_P") (class "Default")
      (node (ref "U1") (pin "L16") (pinfunction "IO_L11P_T1_SRCC_35_L16") (pintype "passive"))
    )
    (net (code "68") (name "/B35_L7_N") (class "Default")
      (node (ref "U1") (pin "M15") (pinfunction "IO_L23N_T3_35_M15") (pintype "passive"))
    )
    (net (code "69") (name "/B35_L7_P") (class "Default")
      (node (ref "U1") (pin "M14") (pinfunction "IO_L23P_T3_35_M14") (pintype "passive"))
    )
    (net (code "70") (name "/B35_L8_N") (class "Default")
      (node (ref "U1") (pin "J19") (pinfunction "IO_L10N_T1_AD11N_35_J19") (pintype "passive"))
    )
    (net (code "71") (name "/B35_L8_P") (class "Default")
      (node (ref "U1") (pin "K19") (pinfunction "IO_L10P_T1_AD11P_35_K19") (pintype "passive"))
    )
    (net (code "72") (name "/B35_L9_N") (class "Default")
      (node (ref "U1") (pin "H18") (pinfunction "IO_L14N_T2_AD4N_MRCC_35_H18") (pintype "passive"))
    )
    (net (code "73") (name "/B35_L9_P") (class "Default")
      (node (ref "U1") (pin "J18") (pinfunction "IO_L14P_T2_AD4P_MRCC_35_J18") (pintype "passive"))
    )
    (net (code "74") (name "/B35_L10_N") (class "Default")
      (node (ref "U1") (pin "G18") (pinfunction "IO_L16N_T2_35_G18") (pintype "passive"))
    )
    (net (code "75") (name "/B35_L10_P") (class "Default")
      (node (ref "U1") (pin "G17") (pinfunction "IO_L16P_T2_35_G17") (pintype "passive"))
    )
    (net (code "76") (name "/B35_L11_N") (class "Default")
      (node (ref "U1") (pin "H17") (pinfunction "IO_L13N_T2_MRCC_35_H17") (pintype "passive"))
    )
    (net (code "77") (name "/B35_L11_P") (class "Default")
      (node (ref "U1") (pin "H16") (pinfunction "IO_L13P_T2_MRCC_35_H16") (pintype "passive"))
    )
    (net (code "78") (name "/B35_L12_N") (class "Default")
      (node (ref "U1") (pin "L15") (pinfunction "IO_L22N_T3_AD7N_35_L15") (pintype "passive"))
    )
    (net (code "79") (name "/B35_L12_P") (class "Default")
      (node (ref "U1") (pin "L14") (pinfunction "IO_L22P_T3_AD7P_35_L14") (pintype "passive"))
    )
    (net (code "80") (name "/B35_L13_N") (class "Default")
      (node (ref "U1") (pin "M20") (pinfunction "IO_L7N_T1_AD2N_35_M20") (pintype "passive"))
    )
    (net (code "81") (name "/B35_L13_P") (class "Default")
      (node (ref "U1") (pin "M19") (pinfunction "IO_L7P_T1_AD2P_35_M19") (pintype "passive"))
    )
    (net (code "82") (name "/B35_L14_N") (class "Default")
      (node (ref "U1") (pin "J14") (pinfunction "IO_L20N_T3_AD6N_35_J14") (pintype "passive"))
    )
    (net (code "83") (name "/B35_L14_P") (class "Default")
      (node (ref "U1") (pin "K14") (pinfunction "IO_L20P_T3_AD6P_35_K14") (pintype "passive"))
    )
    (net (code "84") (name "/B35_L15_N") (class "Default")
      (node (ref "U1") (pin "K18") (pinfunction "IO_L12N_T1_MRCC_35_K18") (pintype "passive"))
    )
    (net (code "85") (name "/B35_L15_P") (class "Default")
      (node (ref "U1") (pin "K17") (pinfunction "IO_L12P_T1_MRCC_35_K17") (pintype "passive"))
    )
    (net (code "86") (name "/B35_L16_N") (class "Default")
      (node (ref "U1") (pin "F17") (pinfunction "IO_L6N_T0_VREF_35_F17") (pintype "passive"))
    )
    (net (code "87") (name "/B35_L16_P") (class "Default")
      (node (ref "U1") (pin "F16") (pinfunction "IO_L6P_TO_35_F16") (pintype "passive"))
    )
    (net (code "88") (name "/B35_L17_N") (class "Default")
      (node (ref "U1") (pin "G20") (pinfunction "IO_L18N_T2_AD13N_35_G20") (pintype "passive"))
    )
    (net (code "89") (name "/B35_L17_P") (class "Default")
      (node (ref "U1") (pin "G19") (pinfunction "IO_L18P_T2__AD13P35_G19") (pintype "passive"))
    )
    (net (code "90") (name "/B35_L18_N") (class "Default")
      (node (ref "U1") (pin "F20") (pinfunction "IO_L15N_T2_DQS_AD12N_35_F20") (pintype "passive"))
    )
    (net (code "91") (name "/B35_L18_P") (class "Default")
      (node (ref "U1") (pin "F19") (pinfunction "IO_L15P_T2_DQS_AD12P_35_F19") (pintype "passive"))
    )
    (net (code "92") (name "/B35_L19_N") (class "Default")
      (node (ref "U1") (pin "E19") (pinfunction "IO_L5N_TO_AD9N_35_E19") (pintype "passive"))
    )
    (net (code "93") (name "/B35_L19_P") (class "Default")
      (node (ref "U1") (pin "E18") (pinfunction "IO_L5P_T0_AD9P_35_E18") (pintype "passive"))
    )
    (net (code "94") (name "/B35_L20_N") (class "Default")
      (node (ref "U1") (pin "D18") (pinfunction "IO_L3N_T0_DQS_AD1N_35_D18") (pintype "passive"))
    )
    (net (code "95") (name "/B35_L20_P") (class "Default")
      (node (ref "U1") (pin "E17") (pinfunction "IO_L3P_T0_DQS_AD1P_35_E17") (pintype "passive"))
    )
    (net (code "96") (name "/B35_L21_N") (class "Default")
      (node (ref "U1") (pin "B20") (pinfunction "IO_L1N_T0_AD0N_35_B20") (pintype "passive"))
    )
    (net (code "97") (name "/B35_L21_P") (class "Default")
      (node (ref "U1") (pin "C20") (pinfunction "IO_L1P_T0_AD0P_35_C20") (pintype "passive"))
    )
    (net (code "98") (name "/B35_L22_N") (class "Default")
      (node (ref "U1") (pin "A20") (pinfunction "IO_L2N_T0_AD8N_35_A20") (pintype "passive"))
    )
    (net (code "99") (name "/B35_L22_P") (class "Default")
      (node (ref "U1") (pin "B19") (pinfunction "IO_L2P_T0_AD8P_35_B19") (pintype "passive"))
    )
    (net (code "100") (name "/B35_L23_N") (class "Default")
      (node (ref "U1") (pin "D20") (pinfunction "IO_L4N_TO_35_D20") (pintype "passive"))
    )
    (net (code "101") (name "/B35_L23_P") (class "Default")
      (node (ref "U1") (pin "D19") (pinfunction "IO_L4P_TO_35_D19") (pintype "passive"))
    )
    (net (code "102") (name "/B35_L24_P") (class "Default")
      (node (ref "U1") (pin "K16") (pinfunction "IO_L24P_T3_AD15P_35_K16") (pintype "passive"))
    )
    (net (code "103") (name "/DDR3_A0") (class "Default")
      (node (ref "U1") (pin "N2") (pinfunction "PS_DDR_A0_502_N2") (pintype "passive"))
    )
    (net (code "104") (name "/DDR3_A1") (class "Default")
      (node (ref "U1") (pin "K2") (pinfunction "PS_DDR_A1_502_K2") (pintype "passive"))
    )
    (net (code "105") (name "/DDR3_A2") (class "Default")
      (node (ref "U1") (pin "M3") (pinfunction "PS_DDR_A2_502_M3") (pintype "passive"))
    )
    (net (code "106") (name "/DDR3_A3") (class "Default")
      (node (ref "U1") (pin "K3") (pinfunction "PS_DDR_A3_502_K3") (pintype "passive"))
    )
    (net (code "107") (name "/DDR3_A4") (class "Default")
      (node (ref "U1") (pin "M4") (pinfunction "PS_DDR_A4_502_M4") (pintype "passive"))
    )
    (net (code "108") (name "/DDR3_A5") (class "Default")
      (node (ref "U1") (pin "L1") (pinfunction "PS_DDR_A5_502_L1") (pintype "passive"))
    )
    (net (code "109") (name "/DDR3_A6") (class "Default")
      (node (ref "U1") (pin "L4") (pinfunction "PS_DDR_A6_502_L4") (pintype "passive"))
    )
    (net (code "110") (name "/DDR3_A7") (class "Default")
      (node (ref "U1") (pin "K4") (pinfunction "PS_DDR_A7_502_K4") (pintype "passive"))
    )
    (net (code "111") (name "/DDR3_A8") (class "Default")
      (node (ref "U1") (pin "K1") (pinfunction "PS_DDR_A8_502_K1") (pintype "passive"))
    )
    (net (code "112") (name "/DDR3_A9") (class "Default")
      (node (ref "U1") (pin "J4") (pinfunction "PS_DDR_A9_502_J4") (pintype "passive"))
    )
    (net (code "113") (name "/DDR3_A10") (class "Default")
      (node (ref "U1") (pin "F5") (pinfunction "PS_DDR_A10_502_F5") (pintype "passive"))
    )
    (net (code "114") (name "/DDR3_A11") (class "Default")
      (node (ref "U1") (pin "G4") (pinfunction "PS_DDR_A11_502_G4") (pintype "passive"))
    )
    (net (code "115") (name "/DDR3_A12") (class "Default")
      (node (ref "U1") (pin "E4") (pinfunction "PS_DDR_A12_502_E4") (pintype "passive"))
    )
    (net (code "116") (name "/DDR3_A13") (class "Default")
      (node (ref "U1") (pin "D4") (pinfunction "PS_DDR_A13_502_D4") (pintype "passive"))
    )
    (net (code "117") (name "/DDR3_A14") (class "Default")
      (node (ref "U1") (pin "F4") (pinfunction "PS_DDR_A14_502_F4") (pintype "passive"))
    )
    (net (code "118") (name "/DDR3_BA0") (class "Default")
      (node (ref "U1") (pin "L5") (pinfunction "PS_DDR_BA0_502_L5") (pintype "passive"))
    )
    (net (code "119") (name "/DDR3_BA1") (class "Default")
      (node (ref "U1") (pin "R4") (pinfunction "PS_DDR_BA1_502_R4") (pintype "passive"))
    )
    (net (code "120") (name "/DDR3_BA2") (class "Default")
      (node (ref "U1") (pin "J5") (pinfunction "PS_DDR_BA2_502_J5") (pintype "passive"))
    )
    (net (code "121") (name "/DDR3_CAS") (class "Default")
      (node (ref "U1") (pin "P5") (pinfunction "PS_DDR_CAS_B_502_P5") (pintype "passive"))
    )
    (net (code "122") (name "/DDR3_CKE") (class "Default")
      (node (ref "U1") (pin "N3") (pinfunction "PS_DDR_CKE_502_N3") (pintype "passive"))
    )
    (net (code "123") (name "/DDR3_CLK0_N") (class "Default")
      (node (ref "U1") (pin "M2") (pinfunction "PS_DDR_CKN_502_M2") (pintype "passive"))
    )
    (net (code "124") (name "/DDR3_CLK0_P") (class "Default")
      (node (ref "U1") (pin "L2") (pinfunction "PS_DDR_CKP_502_L2") (pintype "passive"))
    )
    (net (code "125") (name "/DDR3_D0") (class "Default")
      (node (ref "U1") (pin "C3") (pinfunction "PS_DDR_DQ0_502_C3") (pintype "passive"))
    )
    (net (code "126") (name "/DDR3_D1") (class "Default")
      (node (ref "U1") (pin "B3") (pinfunction "PS_DDR_DQ1_502_B3") (pintype "passive"))
    )
    (net (code "127") (name "/DDR3_D2") (class "Default")
      (node (ref "U1") (pin "A2") (pinfunction "PS_DDR_DQ2_502_A2") (pintype "passive"))
    )
    (net (code "128") (name "/DDR3_D3") (class "Default")
      (node (ref "U1") (pin "A4") (pinfunction "PS_DDR_DQ3_502_A4") (pintype "passive"))
    )
    (net (code "129") (name "/DDR3_D4") (class "Default")
      (node (ref "U1") (pin "D3") (pinfunction "PS_DDR_DQ4_502_D3") (pintype "passive"))
    )
    (net (code "130") (name "/DDR3_D5") (class "Default")
      (node (ref "U1") (pin "D1") (pinfunction "PS_DDR_DQ5_502_D1") (pintype "passive"))
    )
    (net (code "131") (name "/DDR3_D6") (class "Default")
      (node (ref "U1") (pin "C1") (pinfunction "PS_DDR_DQ6_502_C1") (pintype "passive"))
    )
    (net (code "132") (name "/DDR3_D7") (class "Default")
      (node (ref "U1") (pin "E1") (pinfunction "PS_DDR_DQ7_502_E1") (pintype "passive"))
    )
    (net (code "133") (name "/DDR3_D8") (class "Default")
      (node (ref "U1") (pin "E2") (pinfunction "PS_DDR_DQ8_502_E2") (pintype "passive"))
    )
    (net (code "134") (name "/DDR3_D9") (class "Default")
      (node (ref "U1") (pin "E3") (pinfunction "PS_DDR_DQ9_502_E3") (pintype "passive"))
    )
    (net (code "135") (name "/DDR3_D10") (class "Default")
      (node (ref "U1") (pin "G3") (pinfunction "PS_DDR_DQ10_502_G3") (pintype "passive"))
    )
    (net (code "136") (name "/DDR3_D11") (class "Default")
      (node (ref "U1") (pin "H3") (pinfunction "PS_DDR_DQ11_502_H3") (pintype "passive"))
    )
    (net (code "137") (name "/DDR3_D12") (class "Default")
      (node (ref "U1") (pin "J3") (pinfunction "PS_DDR_DQ12_502_J3") (pintype "passive"))
    )
    (net (code "138") (name "/DDR3_D13") (class "Default")
      (node (ref "U1") (pin "H2") (pinfunction "PS_DDR_DQ13_502_H2") (pintype "passive"))
    )
    (net (code "139") (name "/DDR3_D14") (class "Default")
      (node (ref "U1") (pin "H1") (pinfunction "PS_DDR_DQ14_502_H1") (pintype "passive"))
    )
    (net (code "140") (name "/DDR3_D15") (class "Default")
      (node (ref "U1") (pin "J1") (pinfunction "PS_DDR_DQ15_502_J1") (pintype "passive"))
    )
    (net (code "141") (name "/DDR3_D16") (class "Default")
      (node (ref "U1") (pin "P1") (pinfunction "PS_DDR_DQ16_502_P1") (pintype "passive"))
    )
    (net (code "142") (name "/DDR3_D17") (class "Default")
      (node (ref "U1") (pin "P3") (pinfunction "PS_DDR_DQ17_502_P3") (pintype "passive"))
    )
    (net (code "143") (name "/DDR3_D18") (class "Default")
      (node (ref "U1") (pin "R3") (pinfunction "PS_DDR_DQ18_502_R3") (pintype "passive"))
    )
    (net (code "144") (name "/DDR3_D19") (class "Default")
      (node (ref "U1") (pin "R1") (pinfunction "PS_DDR_DQ19_502_R1") (pintype "passive"))
    )
    (net (code "145") (name "/DDR3_D20") (class "Default")
      (node (ref "U1") (pin "T4") (pinfunction "PS_DDR_DQ20_502_T4") (pintype "passive"))
    )
    (net (code "146") (name "/DDR3_D21") (class "Default")
      (node (ref "U1") (pin "U4") (pinfunction "PS_DDR_DQ21_502_U4") (pintype "passive"))
    )
    (net (code "147") (name "/DDR3_D22") (class "Default")
      (node (ref "U1") (pin "U2") (pinfunction "PS_DDR_DQ21_502_U2") (pintype "passive"))
    )
    (net (code "148") (name "/DDR3_D23") (class "Default")
      (node (ref "U1") (pin "U3") (pinfunction "PS_DDR_DQ23_502_U3") (pintype "passive"))
    )
    (net (code "149") (name "/DDR3_D24") (class "Default")
      (node (ref "U1") (pin "V1") (pinfunction "PS_DDR_DQ24_502_V1") (pintype "passive"))
    )
    (net (code "150") (name "/DDR3_D25") (class "Default")
      (node (ref "U1") (pin "Y3") (pinfunction "PS_DDR_DQ25_502_Y3") (pintype "passive"))
    )
    (net (code "151") (name "/DDR3_D26") (class "Default")
      (node (ref "U1") (pin "W1") (pinfunction "PS_DDR_DQ26_502_W1") (pintype "passive"))
    )
    (net (code "152") (name "/DDR3_D27") (class "Default")
      (node (ref "U1") (pin "Y4") (pinfunction "PS_DDR_DQ27_502_Y4") (pintype "passive"))
    )
    (net (code "153") (name "/DDR3_D28") (class "Default")
      (node (ref "U1") (pin "Y2") (pinfunction "PS_DDR_DQ28_502_Y2") (pintype "passive"))
    )
    (net (code "154") (name "/DDR3_D29") (class "Default")
      (node (ref "U1") (pin "W3") (pinfunction "PS_DDR_DQ29_502_W3") (pintype "passive"))
    )
    (net (code "155") (name "/DDR3_D30") (class "Default")
      (node (ref "U1") (pin "V2") (pinfunction "PS_DDR_DQ30_502_V2") (pintype "passive"))
    )
    (net (code "156") (name "/DDR3_D31") (class "Default")
      (node (ref "U1") (pin "V3") (pinfunction "PS_DDR_DQ31_502_V3") (pintype "passive"))
    )
    (net (code "157") (name "/DDR3_DM0") (class "Default")
      (node (ref "U1") (pin "A1") (pinfunction "PS_DDR_DM0_502_A1") (pintype "passive"))
    )
    (net (code "158") (name "/DDR3_DM1") (class "Default")
      (node (ref "U1") (pin "F1") (pinfunction "PS_DDR_DM1_502_F1") (pintype "passive"))
    )
    (net (code "159") (name "/DDR3_DM2") (class "Default")
      (node (ref "U1") (pin "T1") (pinfunction "PS_DDR_DM2_502_T1") (pintype "passive"))
    )
    (net (code "160") (name "/DDR3_DM3") (class "Default")
      (node (ref "U1") (pin "Y1") (pinfunction "PS_DDR_DM3_502_Y1") (pintype "passive"))
    )
    (net (code "161") (name "/DDR3_DQS0_N") (class "Default")
      (node (ref "U1") (pin "B2") (pinfunction "PS_DDR_DQS_N0_502_B2") (pintype "passive"))
    )
    (net (code "162") (name "/DDR3_DQS0_P") (class "Default")
      (node (ref "U1") (pin "C2") (pinfunction "PS_DDR_DQS_P0_502_C2") (pintype "passive"))
    )
    (net (code "163") (name "/DDR3_DQS1_N") (class "Default")
      (node (ref "U1") (pin "F2") (pinfunction "PS_DDR_DQS_N1_502_F2") (pintype "passive"))
    )
    (net (code "164") (name "/DDR3_DQS1_P") (class "Default")
      (node (ref "U1") (pin "G2") (pinfunction "PS_DDR_DQS_P1_502_G2") (pintype "passive"))
    )
    (net (code "165") (name "/DDR3_DQS2_N") (class "Default")
      (node (ref "U1") (pin "T2") (pinfunction "PS_DDR_DQS_N2_502_T2") (pintype "passive"))
    )
    (net (code "166") (name "/DDR3_DQS2_P") (class "Default")
      (node (ref "U1") (pin "R2") (pinfunction "PS_DDR_DQS_P2_502_R2") (pintype "passive"))
    )
    (net (code "167") (name "/DDR3_DQS3_N") (class "Default")
      (node (ref "U1") (pin "W4") (pinfunction "PS_DDR_DQS_N3_502_W4") (pintype "passive"))
    )
    (net (code "169") (name "/DDR3_ODT") (class "Default")
      (node (ref "U1") (pin "N5") (pinfunction "PS_DDR_ODT_502_N5") (pintype "passive"))
    )
    (net (code "170") (name "/DDR3_RAS") (class "Default")
      (node (ref "U1") (pin "P4") (pinfunction "PS_DDR_RAS_B_502_P4") (pintype "passive"))
    )
    (net (code "171") (name "/DDR3_RESET") (class "Default")
      (node (ref "U1") (pin "B4") (pinfunction "PS_DDR_DRST_B_502_B4") (pintype "passive"))
    )
    (net (code "172") (name "/DDR3_S0") (class "Default")
      (node (ref "U1") (pin "N1") (pinfunction "PS_DDR_CS_B_502_N1") (pintype "passive"))
    )
    (net (code "173") (name "/DDR3_VRN") (class "Default")
      (node (ref "R27") (pin "1") (pinfunction "1_1") (pintype "passive"))
      (node (ref "U1") (pin "G5") (pinfunction "PS_DDR_VRN_502_G5") (pintype "passive"))
    )
    (net (code "174") (name "/DDR3_VRP") (class "Default")
      (node (ref "R26") (pin "1") (pinfunction "1_1") (pintype "passive"))
      (node (ref "U1") (pin "H5") (pinfunction "PS_DDR_VRP_502_H5") (pintype "passive"))
    )
    (net (code "175") (name "/DDR3_WE") (class "Default")
      (node (ref "U1") (pin "M5") (pinfunction "PS_DDR_WE_B_502_M5") (pintype "passive"))
    )
    (net (code "176") (name "/ETH_MDC") (class "Default")
      (node (ref "U1") (pin "C10") (pinfunction "PS_MIO52_501_C10") (pintype "passive"))
    )
    (net (code "177") (name "/ETH_MDIO") (class "Default")
      (node (ref "U1") (pin "C11") (pinfunction "PS_MIO53_501_C11") (pintype "passive"))
    )
    (net (code "178") (name "/ETH_RXCK") (class "Default")
      (node (ref "U1") (pin "B17") (pinfunction "PS_MIO22_501_B17") (pintype "passive"))
    )
    (net (code "179") (name "/ETH_RXCTL") (class "Default")
      (node (ref "U1") (pin "D13") (pinfunction "PS_MIO27_501_D13") (pintype "passive"))
    )
    (net (code "180") (name "/ETH_RXD0") (class "Default")
      (node (ref "U1") (pin "D11") (pinfunction "PS_MIO23_501_D11") (pintype "passive"))
    )
    (net (code "181") (name "/ETH_RXD1") (class "Default")
      (node (ref "U1") (pin "A16") (pinfunction "PS_MIO24_501_A16") (pintype "passive"))
    )
    (net (code "182") (name "/ETH_RXD2") (class "Default")
      (node (ref "U1") (pin "F15") (pinfunction "PS_MIO25_501_F15") (pintype "passive"))
    )
    (net (code "183") (name "/ETH_RXD3") (class "Default")
      (node (ref "U1") (pin "A15") (pinfunction "PS_MIO26_501_A15") (pintype "passive"))
    )
    (net (code "184") (name "/ETH_TXCK") (class "Default")
      (node (ref "U1") (pin "A19") (pinfunction "PS_MIO16_501_A19") (pintype "passive"))
    )
    (net (code "185") (name "/ETH_TXCTL") (class "Default")
      (node (ref "U1") (pin "F14") (pinfunction "PS_MIO21_501_F14") (pintype "passive"))
    )
    (net (code "186") (name "/ETH_TXD0") (class "Default")
      (node (ref "U1") (pin "E14") (pinfunction "PS_MIO17_501_E14") (pintype "passive"))
    )
    (net (code "187") (name "/ETH_TXD1") (class "Default")
      (node (ref "U1") (pin "B18") (pinfunction "PS_MIO18_501_B18") (pintype "passive"))
    )
    (net (code "188") (name "/ETH_TXD2") (class "Default")
      (node (ref "U1") (pin "D10") (pinfunction "PS_MIO19_501_D10") (pintype "passive"))
    )
    (net (code "189") (name "/ETH_TXD3") (class "Default")
      (node (ref "U1") (pin "A17") (pinfunction "PS_MIO20_501_A17") (pintype "passive"))
    )
    (net (code "190") (name "/FPGA_DONE") (class "Default")
      (node (ref "LED4") (pin "2") (pinfunction "2_2") (pintype "passive"))
      (node (ref "R5") (pin "1") (pinfunction "1_1") (pintype "passive"))
      (node (ref "U1") (pin "R11") (pinfunction "DONE_0_R11") (pintype "passive"))
    )
    (net (code "191") (name "/FPGA_TCK") (class "Default")
      (node (ref "J1") (pin "4") (pinfunction "4_4") (pintype "passive"))
      (node (ref "U1") (pin "F9") (pinfunction "TCK_0_F9") (pintype "passive"))
    )
    (net (code "192") (name "/FPGA_TDI") (class "Default")
      (node (ref "J1") (pin "2") (pinfunction "2_2") (pintype "passive"))
      (node (ref "U1") (pin "G6") (pinfunction "TDI_0_G6") (pintype "passive"))
    )
    (net (code "193") (name "/FPGA_TDO") (class "Default")
      (node (ref "J1") (pin "3") (pinfunction "3_3") (pintype "passive"))
      (node (ref "U1") (pin "F6") (pinfunction "TDO_0_F6") (pintype "passive"))
    )
    (net (code "194") (name "/FPGA_TMS") (class "Default")
      (node (ref "J1") (pin "1") (pinfunction "1_1") (pintype "passive"))
      (node (ref "U1") (pin "J6") (pinfunction "TMS_0_J6") (pintype "passive"))
    )
    (net (code "195") (name "/MIO0_LED") (class "Default")
      (node (ref "LED2") (pin "1") (pinfunction "1_1") (pintype "passive"))
      (node (ref "U1") (pin "E6") (pinfunction "PS_MIO0_500_E6") (pintype "passive"))
    )
    (net (code "196") (name "/MMC_CCLK") (class "Default")
      (node (ref "R24") (pin "2") (pinfunction "2_2") (pintype "passive"))
    )
    (net (code "197") (name "/MMC_CMD") (class "Default")
      (node (ref "U1") (pin "B14") (pinfunction "PS_MIO47_501_B14") (pintype "passive"))
    )
    (net (code "198") (name "/MMC_DATA0") (class "Default")
      (node (ref "U1") (pin "D16") (pinfunction "PS_MIO46_501_D16") (pintype "passive"))
    )
    (net (code "199") (name "/MMC_DATA1") (class "Default")
      (node (ref "U1") (pin "C12") (pinfunction "PS_MIO49_501_C12") (pintype "passive"))
    )
    (net (code "200") (name "/MMC_DATA2") (class "Default")
      (node (ref "U1") (pin "B13") (pinfunction "PS_MIO50_501_B13") (pintype "passive"))
    )
    (net (code "201") (name "/MMC_DATA3") (class "Default")
      (node (ref "U1") (pin "B9") (pinfunction "PS_MIO51_501_B9") (pintype "passive"))
    )
    (net (code "202") (name "/OTG_CLK") (class "Default")
      (node (ref "U1") (pin "A11") (pinfunction "PS_MIO36_501_A11") (pintype "passive"))
    )
    (net (code "203") (name "/OTG_DATA0") (class "Default")
      (node (ref "U1") (pin "A14") (pinfunction "PS_MIO32_501_A14") (pintype "passive"))
    )
    (net (code "204") (name "/OTG_DATA1") (class "Default")
      (node (ref "U1") (pin "D15") (pinfunction "PS_MIO33_501_D15") (pintype "passive"))
    )
    (net (code "205") (name "/OTG_DATA2") (class "Default")
      (node (ref "U1") (pin "A12") (pinfunction "PS_MIO34_501_A12") (pintype "passive"))
    )
    (net (code "206") (name "/OTG_DATA3") (class "Default")
      (node (ref "U1") (pin "F12") (pinfunction "PS_MIO35_501_F12") (pintype "passive"))
    )
    (net (code "207") (name "/OTG_DATA4") (class "Default")
      (node (ref "U1") (pin "C16") (pinfunction "PS_MIO28_501_C16") (pintype "passive"))
    )
    (net (code "208") (name "/OTG_DATA5") (class "Default")
      (node (ref "U1") (pin "A10") (pinfunction "PS_MIO37_501_A10") (pintype "passive"))
    )
    (net (code "209") (name "/OTG_DATA6") (class "Default")
      (node (ref "U1") (pin "E13") (pinfunction "PS_MIO38_501_E13") (pintype "passive"))
    )
    (net (code "210") (name "/OTG_DATA7") (class "Default")
      (node (ref "U1") (pin "C18") (pinfunction "PS_MIO39_501_C18") (pintype "passive"))
    )
    (net (code "211") (name "/OTG_DIR") (class "Default")
      (node (ref "U1") (pin "C13") (pinfunction "PS_MIO29_501_C13") (pintype "passive"))
    )
    (net (code "212") (name "/OTG_NXT") (class "Default")
      (node (ref "U1") (pin "E16") (pinfunction "PS_MIO31_501_E16") (pintype "passive"))
    )
    (net (code "213") (name "/OTG_STP") (class "Default")
      (node (ref "U1") (pin "C15") (pinfunction "PS_MIO30_501_C15") (pintype "passive"))
    )
    (net (code "214") (name "/PL_GCLK") (class "Default")
      (node (ref "R7") (pin "2") (pinfunction "2_2") (pintype "passive"))
      (node (ref "U1") (pin "U18") (pinfunction "IO_L12P_T1_MRCC_34_U18") (pintype "passive"))
    )
    (net (code "215") (name "/PL_LED") (class "Default")
      (node (ref "LED1") (pin "1") (pinfunction "1_1") (pintype "passive"))
      (node (ref "U1") (pin "J16") (pinfunction "IO_L24N_T3_AD15N_35_J16") (pintype "passive"))
    )
    (net (code "216") (name "/PS_MIO7") (class "Default")
      (node (ref "R14") (pin "2") (pinfunction "2_2") (pintype "passive"))
      (node (ref "U1") (pin "D8") (pinfunction "PS_MIO7_500_D8") (pintype "passive"))
    )
    (net (code "217") (name "/PS_MIO8") (class "Default")
      (node (ref "R9") (pin "2") (pinfunction "2_2") (pintype "passive"))
      (node (ref "U1") (pin "D5") (pinfunction "PS_MIO8_500_D5") (pintype "passive"))
    )
    (net (code "218") (name "/PS_MIO9") (class "Default")
      (node (ref "U1") (pin "B5") (pinfunction "PS_MIO9_500_B5") (pintype "passive"))
    )
    (net (code "219") (name "/PS_MIO10") (class "Default")
      (node (ref "U1") (pin "E9") (pinfunction "PS_MIO10_500_E9") (pintype "passive"))
    )
    (net (code "220") (name "/PS_MIO11") (class "Default")
      (node (ref "U1") (pin "C6") (pinfunction "PS_MIO11_500_C6") (pintype "passive"))
    )
    (net (code "221") (name "/PS_MIO12") (class "Default")
      (node (ref "U1") (pin "D9") (pinfunction "PS_MIO12_500_D9") (pintype "passive"))
    )
    (net (code "222") (name "/PS_MIO13") (class "Default")
      (node (ref "U1") (pin "E8") (pinfunction "PS_MIO13_500_E8") (pintype "passive"))
    )
    (net (code "223") (name "/PS_POR_B") (class "Default")
      (node (ref "R22") (pin "1") (pinfunction "1_1") (pintype "passive"))
      (node (ref "U1") (pin "C7") (pinfunction "PS_POR_B_500_C7") (pintype "passive"))
      (node (ref "U2") (pin "2") (pinfunction "~{RESET}_2") (pintype "passive"))
    )
    (net (code "224") (name "/PS_SRST_B") (class "Default")
      (node (ref "R25") (pin "1") (pinfunction "1_1") (pintype "passive"))
      (node (ref "U1") (pin "B10") (pinfunction "PS_SRST_B_501_B_B10") (pintype "passive"))
    )
    (net (code "225") (name "/QSPI_CS") (class "Default")
      (node (ref "U1") (pin "A7") (pinfunction "PS_MIO1_500_A7") (pintype "passive"))
    )
    (net (code "226") (name "/QSPI_D0") (class "Default")
      (node (ref "R10") (pin "2") (pinfunction "2_2") (pintype "passive"))
      (node (ref "U1") (pin "B8") (pinfunction "PS_MIO2_500_B8") (pintype "passive"))
    )
    (net (code "227") (name "/QSPI_D1") (class "Default")
      (node (ref "R11") (pin "2") (pinfunction "2_2") (pintype "passive"))
      (node (ref "U1") (pin "D6") (pinfunction "PS_MIO3_500_D6") (pintype "passive"))
    )
    (net (code "228") (name "/QSPI_D2") (class "Default")
      (node (ref "U1") (pin "B7") (pinfunction "PS_MIO4_500_B7") (pintype "passive"))
    )
    (net (code "229") (name "/QSPI_D3") (class "Default")
      (node (ref "U1") (pin "A6") (pinfunction "PS_MIO5_500_A6") (pintype "passive"))
    )
    (net (code "230") (name "/QSPI_SCK") (class "Default")
      (node (ref "R12") (pin "2") (pinfunction "2_2") (pintype "passive"))
      (node (ref "R13") (pin "1") (pinfunction "1_1") (pintype "passive"))
    )
    (net (code "231") (name "/SD_CLK") (class "Default")
      (node (ref "R23") (pin "2") (pinfunction "2_2") (pintype "passive"))
    )
    (net (code "232") (name "/SD_CMD") (class "Default")
      (node (ref "U1") (pin "C17") (pinfunction "PS_MIO41_501_C17") (pintype "passive"))
    )
    (net (code "233") (name "/SD_D0") (class "Default")
      (node (ref "U1") (pin "E12") (pinfunction "PS_MIO42_501_E12") (pintype "passive"))
    )
    (net (code "234") (name "/SD_D1") (class "Default")
      (node (ref "U1") (pin "A9") (pinfunction "PS_MIO43_501_A9") (pintype "passive"))
    )
    (net (code "235") (name "/SD_D2") (class "Default")
      (node (ref "U1") (pin "F13") (pinfunction "PS_MIO44_501_F13") (pintype "passive"))
    )
    (net (code "236") (name "/SD_D3") (class "Default")
      (node (ref "U1") (pin "B15") (pinfunction "PS_MIO45_501_B15") (pintype "passive"))
    )
    (net (code "237") (name "/UART_RXD") (class "Default")
      (node (ref "U1") (pin "C5") (pinfunction "PS_MIO14_500_C5") (pintype "passive"))
    )
    (net (code "238") (name "/UART_TXD") (class "Default")
      (node (ref "U1") (pin "C8") (pinfunction "PS_MIO15_500_C8") (pintype "passive"))
    )
    (net (code "239") (name "/XADC_VN") (class "Default")
      (node (ref "U1") (pin "L10") (pinfunction "VN_0_L10") (pintype "passive"))
    )
    (net (code "240") (name "/XADC_VP") (class "Default")
      (node (ref "U1") (pin "K9") (pinfunction "VP_0_K9") (pintype "passive"))
    )
    (net (code "241") (name "AGND") (class "Default")
      (node (ref "C1") (pin "1") (pinfunction "1_1") (pintype "passive"))
      (node (ref "C2") (pin "1") (pinfunction "1_1") (pintype "passive"))
      (node (ref "L2") (pin "2") (pinfunction "2_2") (pintype "passive"))
      (node (ref "U1") (pin "J10") (pinfunction "GNDADC_0_J10") (pintype "passive"))
      (node (ref "U1") (pin "K10") (pinfunction "VREFN_0_K10") (pintype "passive"))
      (node (ref "U1") (pin "L9") (pinfunction "VREFP_0_L9") (pintype "passive"))
    )
    (net (code "242") (name "AVCC") (class "Default")
      (node (ref "C1") (pin "2") (pinfunction "2_2") (pintype "passive"))
      (node (ref "C2") (pin "2") (pinfunction "2_2") (pintype "passive"))
      (node (ref "L1") (pin "1") (pinfunction "1_1") (pintype "passive"))
      (node (ref "U1") (pin "J9") (pinfunction "VCCADC_0_J9") (pintype "passive"))
    )
    (net (code "243") (name "GND") (class "Default")
      (node (ref "C10") (pin "1") (pinfunction "1_1") (pintype "passive"))
      (node (ref "C11") (pin "1") (pinfunction "1_1") (pintype "passive"))
      (node (ref "C12") (pin "1") (pinfunction "1_1") (pintype "passive"))
      (node (ref "C13") (pin "1") (pinfunction "1_1") (pintype "passive"))
      (node (ref "C14") (pin "1") (pinfunction "1_1") (pintype "passive"))
      (node (ref "C15") (pin "1") (pinfunction "1_1") (pintype "passive"))
      (node (ref "C16") (pin "1") (pinfunction "1_1") (pintype "passive"))
      (node (ref "C17") (pin "1") (pinfunction "1_1") (pintype "passive"))
      (node (ref "C18") (pin "1") (pinfunction "1_1") (pintype "passive"))
      (node (ref "C19") (pin "1") (pinfunction "1_1") (pintype "passive"))
      (node (ref "C20") (pin "1") (pinfunction "1_1") (pintype "passive"))
      (node (ref "C21") (pin "1") (pinfunction "1_1") (pintype "passive"))
      (node (ref "C22") (pin "1") (pinfunction "1_1") (pintype "passive"))
      (node (ref "C23") (pin "1") (pinfunction "1_1") (pintype "passive"))
      (node (ref "C24") (pin "1") (pinfunction "1_1") (pintype "passive"))
      (node (ref "C25") (pin "1") (pinfunction "1_1") (pintype "passive"))
      (node (ref "C26") (pin "1") (pinfunction "1_1") (pintype "passive"))
      (node (ref "C27") (pin "1") (pinfunction "1_1") (pintype "passive"))
      (node (ref "C28") (pin "1") (pinfunction "1_1") (pintype "passive"))
      (node (ref "C29") (pin "1") (pinfunction "1_1") (pintype "passive"))
      (node (ref "C3") (pin "1") (pinfunction "1_1") (pintype "passive"))
      (node (ref "C30") (pin "1") (pinfunction "1_1") (pintype "passive"))
      (node (ref "C31") (pin "1") (pinfunction "1_1") (pintype "passive"))
      (node (ref "C32") (pin "1") (pinfunction "1_1") (pintype "passive"))
      (node (ref "C33") (pin "1") (pinfunction "1_1") (pintype "passive"))
      (node (ref "C34") (pin "1") (pinfunction "1_1") (pintype "passive"))
      (node (ref "C35") (pin "1") (pinfunction "1_1") (pintype "passive"))
      (node (ref "C36") (pin "1") (pinfunction "1_1") (pintype "passive"))
      (node (ref "C37") (pin "1") (pinfunction "1_1") (pintype "passive"))
      (node (ref "C38") (pin "1") (pinfunction "1_1") (pintype "passive"))
      (node (ref "C39") (pin "1") (pinfunction "1_1") (pintype "passive"))
      (node (ref "C4") (pin "2") (pinfunction "2_2") (pintype "passive"))
      (node (ref "C40") (pin "1") (pinfunction "1_1") (pintype "passive"))
      (node (ref "C41") (pin "1") (pinfunction "1_1") (pintype "passive"))
      (node (ref "C42") (pin "1") (pinfunction "1_1") (pintype "passive"))
      (node (ref "C43") (pin "1") (pinfunction "1_1") (pintype "passive"))
      (node (ref "C44") (pin "1") (pinfunction "1_1") (pintype "passive"))
      (node (ref "C45") (pin "1") (pinfunction "1_1") (pintype "passive"))
      (node (ref "C46") (pin "1") (pinfunction "1_1") (pintype "passive"))
      (node (ref "C47") (pin "1") (pinfunction "1_1") (pintype "passive"))
      (node (ref "C48") (pin "1") (pinfunction "1_1") (pintype "passive"))
      (node (ref "C49") (pin "1") (pinfunction "1_1") (pintype "passive"))
      (node (ref "C5") (pin "1") (pinfunction "1_1") (pintype "passive"))
      (node (ref "C50") (pin "1") (pinfunction "1_1") (pintype "passive"))
      (node (ref "C51") (pin "1") (pinfunction "1_1") (pintype "passive"))
      (node (ref "C52") (pin "1") (pinfunction "1_1") (pintype "passive"))
      (node (ref "C53") (pin "1") (pinfunction "1_1") (pintype "passive"))
      (node (ref "C54") (pin "1") (pinfunction "1_1") (pintype "passive"))
      (node (ref "C55") (pin "1") (pinfunction "1_1") (pintype "passive"))
      (node (ref "C56") (pin "1") (pinfunction "1_1") (pintype "passive"))
      (node (ref "C57") (pin "1") (pinfunction "1_1") (pintype "passive"))
      (node (ref "C58") (pin "1") (pinfunction "1_1") (pintype "passive"))
      (node (ref "C59") (pin "1") (pinfunction "1_1") (pintype "passive"))
      (node (ref "C6") (pin "2") (pinfunction "2_2") (pintype "passive"))
      (node (ref "C60") (pin "1") (pinfunction "1_1") (pintype "passive"))
      (node (ref "C61") (pin "1") (pinfunction "1_1") (pintype "passive"))
      (node (ref "C62") (pin "1") (pinfunction "1_1") (pintype "passive"))
      (node (ref "C63") (pin "1") (pinfunction "1_1") (pintype "passive"))
      (node (ref "C64") (pin "1") (pinfunction "1_1") (pintype "passive"))
      (node (ref "C65") (pin "1") (pinfunction "1_1") (pintype "passive"))
      (node (ref "C66") (pin "1") (pinfunction "1_1") (pintype "passive"))
      (node (ref "C67") (pin "1") (pinfunction "1_1") (pintype "passive"))
      (node (ref "C68") (pin "1") (pinfunction "1_1") (pintype "passive"))
      (node (ref "C69") (pin "1") (pinfunction "1_1") (pintype "passive"))
      (node (ref "C7") (pin "1") (pinfunction "1_1") (pintype "passive"))
      (node (ref "C70") (pin "1") (pinfunction "1_1") (pintype "passive"))
      (node (ref "C71") (pin "1") (pinfunction "1_1") (pintype "passive"))
      (node (ref "C72") (pin "1") (pinfunction "1_1") (pintype "passive"))
      (node (ref "C73") (pin "1") (pinfunction "1_1") (pintype "passive"))
      (node (ref "C74") (pin "1") (pinfunction "1_1") (pintype "passive"))
      (node (ref "C75") (pin "1") (pinfunction "1_1") (pintype "passive"))
      (node (ref "C76") (pin "1") (pinfunction "1_1") (pintype "passive"))
      (node (ref "C77") (pin "1") (pinfunction "1_1") (pintype "passive"))
      (node (ref "C78") (pin "1") (pinfunction "1_1") (pintype "passive"))
      (node (ref "C79") (pin "1") (pinfunction "1_1") (pintype "passive"))
      (node (ref "C8") (pin "1") (pinfunction "1_1") (pintype "passive"))
      (node (ref "C80") (pin "1") (pinfunction "1_1") (pintype "passive"))
      (node (ref "C81") (pin "1") (pinfunction "1_1") (pintype "passive"))
      (node (ref "C82") (pin "1") (pinfunction "1_1") (pintype "passive"))
      (node (ref "C83") (pin "1") (pinfunction "1_1") (pintype "passive"))
      (node (ref "C84") (pin "1") (pinfunction "1_1") (pintype "passive"))
      (node (ref "C85") (pin "1") (pinfunction "1_1") (pintype "passive"))
      (node (ref "C86") (pin "1") (pinfunction "1_1") (pintype "passive"))
      (node (ref "C87") (pin "1") (pinfunction "1_1") (pintype "passive"))
      (node (ref "C88") (pin "1") (pinfunction "1_1") (pintype "passive"))
      (node (ref "C9") (pin "1") (pinfunction "1_1") (pintype "passive"))
      (node (ref "J1") (pin "5") (pinfunction "5_5") (pintype "passive"))
      (node (ref "KEY1") (pin "1") (pinfunction "1_1") (pintype "passive"))
      (node (ref "L2") (pin "1") (pinfunction "1_1") (pintype "passive"))
      (node (ref "R10") (pin "1") (pinfunction "1_1") (pintype "passive"))
      (node (ref "R11") (pin "1") (pinfunction "1_1") (pintype "passive"))
      (node (ref "R12") (pin "1") (pinfunction "1_1") (pintype "passive"))
      (node (ref "R14") (pin "1") (pinfunction "1_1") (pintype "passive"))
      (node (ref "R21") (pin "1") (pinfunction "1_1") (pintype "passive"))
      (node (ref "R26") (pin "2") (pinfunction "2_2") (pintype "passive"))
      (node (ref "R3") (pin "2") (pinfunction "2_2") (pintype "passive"))
      (node (ref "R4") (pin "2") (pinfunction "2_2") (pintype "passive"))
      (node (ref "R5") (pin "2") (pinfunction "2_2") (pintype "passive"))
      (node (ref "R6") (pin "2") (pinfunction "2_2") (pintype "passive"))
      (node (ref "R8") (pin "1") (pinfunction "1_1") (pintype "passive"))
      (node (ref "U1") (pin "A18") (pinfunction "GND51_A18") (pintype "passive"))
      (node (ref "U1") (pin "A8") (pinfunction "GND50_A8") (pintype "passive"))
      (node (ref "U1") (pin "B1") (pinfunction "GND52_B1") (pintype "passive"))
      (node (ref "U1") (pin "B11") (pinfunction "GND53_B11") (pintype "passive"))
      (node (ref "U1") (pin "C14") (pinfunction "GND55_C14") (pintype "passive"))
      (node (ref "U1") (pin "C4") (pinfunction "GND54_C4") (pintype "passive"))
      (node (ref "U1") (pin "C9") (pinfunction "GND35_C9") (pintype "passive"))
      (node (ref "U1") (pin "D17") (pinfunction "GND57_D17") (pintype "passive"))
      (node (ref "U1") (pin "E10") (pinfunction "GND58_E10") (pintype "passive"))
      (node (ref "U1") (pin "E20") (pinfunction "GND59_E20") (pintype "passive"))
      (node (ref "U1") (pin "F10") (pinfunction "RSVDGND_F10") (pintype "passive"))
      (node (ref "U1") (pin "F3") (pinfunction "GND45_F3") (pintype "passive"))
      (node (ref "U1") (pin "F7") (pinfunction "GND46_F7") (pintype "passive"))
      (node (ref "U1") (pin "G10") (pinfunction "GND47_G10") (pintype "passive"))
      (node (ref "U1") (pin "G12") (pinfunction "GND48_G12") (pintype "passive"))
      (node (ref "U1") (pin "G16") (pinfunction "GND49_G16") (pintype "passive"))
      (node (ref "U1") (pin "H11") (pinfunction "GND42_H11") (pintype "passive"))
      (node (ref "U1") (pin "H13") (pinfunction "GND43_H13") (pintype "passive"))
      (node (ref "U1") (pin "H19") (pinfunction "GND44_H19") (pintype "passive"))
      (node (ref "U1") (pin "H7") (pinfunction "GND40_H7") (pintype "passive"))
      (node (ref "U1") (pin "H9") (pinfunction "GND41_H9") (pintype "passive"))
      (node (ref "U1") (pin "J12") (pinfunction "GND32_J12") (pintype "passive"))
      (node (ref "U1") (pin "J2") (pinfunction "GND30_J2") (pintype "passive"))
      (node (ref "U1") (pin "J8") (pinfunction "GND31_J8") (pintype "passive"))
      (node (ref "U1") (pin "K11") (pinfunction "GND56_K11") (pintype "passive"))
      (node (ref "U1") (pin "K13") (pinfunction "GND36_K13") (pintype "passive"))
      (node (ref "U1") (pin "K15") (pinfunction "GND37_K15") (pintype "passive"))
      (node (ref "U1") (pin "K5") (pinfunction "GND33_K5") (pintype "passive"))
      (node (ref "U1") (pin "K7") (pinfunction "GND34_K7") (pintype "passive"))
      (node (ref "U1") (pin "L12") (pinfunction "GND39_L12") (pintype "passive"))
      (node (ref "U1") (pin "L18") (pinfunction "GND20_L18") (pintype "passive"))
      (node (ref "U1") (pin "L8") (pinfunction "GND38_L8") (pintype "passive"))
      (node (ref "U1") (pin "M1") (pinfunction "GND21_M1") (pintype "passive"))
      (node (ref "U1") (pin "M10") (pinfunction "DXN_0_M10") (pintype "passive"))
      (node (ref "U1") (pin "M11") (pinfunction "GND23_M11") (pintype "passive"))
      (node (ref "U1") (pin "M13") (pinfunction "GND24_M13") (pintype "passive"))
      (node (ref "U1") (pin "M7") (pinfunction "GND22_M7") (pintype "passive"))
      (node (ref "U1") (pin "M9") (pinfunction "DXP_0_M9") (pintype "passive"))
      (node (ref "U1") (pin "N10") (pinfunction "GND27_N10") (pintype "passive"))
      (node (ref "U1") (pin "N12") (pinfunction "GND28_N12") (pintype "passive"))
      (node (ref "U1") (pin "N14") (pinfunction "GND29_N14") (pintype "passive"))
      (node (ref "U1") (pin "N4") (pinfunction "GND25_N4") (pintype "passive"))
      (node (ref "U1") (pin "N8") (pinfunction "GND26_N8") (pintype "passive"))
      (node (ref "U1") (pin "P11") (pinfunction "GND17_P11") (pintype "passive"))
      (node (ref "U1") (pin "P13") (pinfunction "GND18_P13") (pintype "passive"))
      (node (ref "U1") (pin "P17") (pinfunction "GND19_P17") (pintype "passive"))
      (node (ref "U1") (pin "P7") (pinfunction "GND15_P7") (pintype "passive"))
      (node (ref "U1") (pin "P9") (pinfunction "GND16_P9") (pintype "passive"))
      (node (ref "U1") (pin "R12") (pinfunction "GND11_R12") (pintype "passive"))
      (node (ref "U1") (pin "R20") (pinfunction "GND12_R20") (pintype "passive"))
      (node (ref "U1") (pin "R8") (pinfunction "GND10_R8") (pintype "passive"))
      (node (ref "U1") (pin "T13") (pinfunction "GND1_T13") (pintype "passive"))
      (node (ref "U1") (pin "T3") (pinfunction "GND13_T3") (pintype "passive"))
      (node (ref "U1") (pin "T7") (pinfunction "GND14_T7") (pintype "passive"))
      (node (ref "U1") (pin "U16") (pinfunction "GND3_U16") (pintype "passive"))
      (node (ref "U1") (pin "U6") (pinfunction "GND2_U6") (pintype "passive"))
      (node (ref "U1") (pin "V19") (pinfunction "GND5_V19") (pintype "passive"))
      (node (ref "U1") (pin "V9") (pinfunction "GND4_V9") (pintype "passive"))
      (node (ref "U1") (pin "W12") (pinfunction "GND7_W12") (pintype "passive"))
      (node (ref "U1") (pin "W2") (pinfunction "GND6_W2") (pintype "passive"))
      (node (ref "U1") (pin "Y15") (pinfunction "GND9_Y15") (pintype "passive"))
      (node (ref "U1") (pin "Y5") (pinfunction "GND8_Y5") (pintype "passive"))
      (node (ref "U2") (pin "1") (pinfunction "GND_1") (pintype "passive"))
      (node (ref "X1") (pin "2") (pinfunction "GND_2") (pintype "passive"))
      (node (ref "X2") (pin "2") (pinfunction "GND_2") (pintype "passive"))
    )
    (net (code "244") (name "Net-(LED1-Pad2)") (class "Default")
      (node (ref "LED1") (pin "2") (pinfunction "2_2") (pintype "passive"))
      (node (ref "R3") (pin "1") (pinfunction "1_1") (pintype "passive"))
    )
    (net (code "245") (name "Net-(LED2-Pad2)") (class "Default")
      (node (ref "LED2") (pin "2") (pinfunction "2_2") (pintype "passive"))
      (node (ref "R4") (pin "1") (pinfunction "1_1") (pintype "passive"))
    )
    (net (code "246") (name "Net-(LED3-Pad2)") (class "Default")
      (node (ref "LED3") (pin "2") (pinfunction "2_2") (pintype "passive"))
      (node (ref "R6") (pin "1") (pinfunction "1_1") (pintype "passive"))
    )
    (net (code "247") (name "Net-(U1A-INIT_B_0)") (class "Default")
      (node (ref "R1") (pin "1") (pinfunction "1_1") (pintype "passive"))
      (node (ref "U1") (pin "R10") (pinfunction "INIT_B_0_R10") (pintype "passive"))
    )
    (net (code "248") (name "Net-(U1A-PROGRAM_B_0)") (class "Default")
      (node (ref "R2") (pin "1") (pinfunction "1_1") (pintype "passive"))
      (node (ref "U1") (pin "L6") (pinfunction "PROGRAM_B_0_L6") (pintype "passive"))
    )
    (net (code "249") (name "Net-(U1E-PS_CLK_500)") (class "Default")
      (node (ref "R17") (pin "1") (pinfunction "1_1") (pintype "passive"))
      (node (ref "U1") (pin "E7") (pinfunction "PS_CLK_500_E7") (pintype "passive"))
    )
    (net (code "250") (name "Net-(U1E-PS_MIO6_500)") (class "Default")
      (node (ref "R13") (pin "2") (pinfunction "2_2") (pintype "passive"))
      (node (ref "U1") (pin "A5") (pinfunction "PS_MIO6_500_A5") (pintype "passive"))
    )
    (net (code "251") (name "Net-(U1F-PS_MIO40_501)") (class "Default")
      (node (ref "R23") (pin "1") (pinfunction "1_1") (pintype "passive"))
      (node (ref "U1") (pin "D14") (pinfunction "PS_MIO40_501_D14") (pintype "passive"))
    )
    (net (code "252") (name "Net-(U1F-PS_MIO48_501)") (class "Default")
      (node (ref "R24") (pin "1") (pinfunction "1_1") (pintype "passive"))
      (node (ref "U1") (pin "B12") (pinfunction "PS_MIO48_501_B12") (pintype "passive"))
    )
    (net (code "253") (name "Net-(U1F-PS_MIO_VREF_501)") (class "Default")
      (node (ref "C5") (pin "2") (pinfunction "2_2") (pintype "passive"))
      (node (ref "R20") (pin "1") (pinfunction "1_1") (pintype "passive"))
      (node (ref "R21") (pin "2") (pinfunction "2_2") (pintype "passive"))
      (node (ref "U1") (pin "E11") (pinfunction "PS_MIO_VREF_501_E11") (pintype "passive"))
    )
    (net (code "254") (name "Net-(U1H-VCCPLL)") (class "Default")
      (node (ref "C85") (pin "2") (pinfunction "2_2") (pintype "passive"))
      (node (ref "C86") (pin "2") (pinfunction "2_2") (pintype "passive"))
      (node (ref "L3") (pin "1") (pinfunction "1_1") (pintype "passive"))
      (node (ref "U1") (pin "G8") (pinfunction "VCCPLL_G8") (pintype "passive"))
    )
    (net (code "255") (name "Net-(U2-~{MR})") (class "Default")
      (node (ref "KEY1") (pin "2") (pinfunction "2_2") (pintype "passive"))
      (node (ref "U2") (pin "3") (pinfunction "~{MR}_3") (pintype "passive"))
    )
    (net (code "256") (name "Net-(X1-OUT)") (class "Default")
      (node (ref "R7") (pin "1") (pinfunction "1_1") (pintype "passive"))
      (node (ref "X1") (pin "3") (pinfunction "OUT_3") (pintype "passive"))
    )
    (net (code "257") (name "Net-(X2-OUT)") (class "Default")
      (node (ref "R17") (pin "2") (pinfunction "2_2") (pintype "passive"))
      (node (ref "X2") (pin "3") (pinfunction "OUT_3") (pintype "passive"))
    )
    (net (code "258") (name "VCCIO") (class "Default")
      (node (ref "U1") (pin "C19") (pinfunction "VCCO_35_1_C19") (pintype "passive"))
      (node (ref "U1") (pin "F18") (pinfunction "VCCO_35_2_F18") (pintype "passive"))
      (node (ref "U1") (pin "H14") (pinfunction "VCCO_35_3_H14") (pintype "passive"))
      (node (ref "U1") (pin "J17") (pinfunction "VCCO_35_4_J17") (pintype "passive"))
      (node (ref "U1") (pin "K20") (pinfunction "VCCO_35_5_K20") (pintype "passive"))
      (node (ref "U1") (pin "M16") (pinfunction "VCCO_35_6_M16") (pintype "passive"))
    )
    (net (code "259") (name "VTTREF") (class "Default")
      (node (ref "C87") (pin "2") (pinfunction "2_2") (pintype "passive"))
      (node (ref "C88") (pin "2") (pinfunction "2_2") (pintype "passive"))
      (node (ref "U1") (pin "H6") (pinfunction "PS_DDR_VREF0_502_1_H6") (pintype "passive"))
      (node (ref "U1") (pin "P6") (pinfunction "PS_DDR_VREF0_502_2_P6") (pintype "passive"))
    )
    (net (code "260") (name "unconnected-(U1D-IO_L6N_T0_VREF_13-PadV5)") (class "Default")
      (node (ref "U1") (pin "V5") (pinfunction "IO_L6N_T0_VREF_13_V5") (pintype "passive+no_connect"))
    )
    (net (code "261") (name "unconnected-(U1D-IO_L11N_T1_SRCC_13-PadV7)") (class "Default")
      (node (ref "U1") (pin "V7") (pinfunction "IO_L11N_T1_SRCC_13_V7") (pintype "passive+no_connect"))
    )
    (net (code "262") (name "unconnected-(U1D-IO_L11P_T1_SRCC_13-PadU7)") (class "Default")
      (node (ref "U1") (pin "U7") (pinfunction "IO_L11P_T1_SRCC_13_U7") (pintype "passive+no_connect"))
    )
    (net (code "263") (name "unconnected-(U1D-IO_L12N_T1_MRCC_13-PadU10)") (class "Default")
      (node (ref "U1") (pin "U10") (pinfunction "IO_L12N_T1_MRCC_13_U10") (pintype "passive+no_connect"))
    )
    (net (code "264") (name "unconnected-(U1D-IO_L12P_T1_MRCC_13-PadT9)") (class "Default")
      (node (ref "U1") (pin "T9") (pinfunction "IO_L12P_T1_MRCC_13_T9") (pintype "passive+no_connect"))
    )
    (net (code "265") (name "unconnected-(U1D-IO_L13N_T2_MRCC_13-PadY6)") (class "Default")
      (node (ref "U1") (pin "Y6") (pinfunction "IO_L13N_T2_MRCC_13_Y6") (pintype "passive+no_connect"))
    )
    (net (code "266") (name "unconnected-(U1D-IO_L13P_T2_MRCC_13-PadY7)") (class "Default")
      (node (ref "U1") (pin "Y7") (pinfunction "IO_L13P_T2_MRCC_13_Y7") (pintype "passive+no_connect"))
    )
    (net (code "267") (name "unconnected-(U1D-IO_L14N_T2_SRCC_13-PadY8)") (class "Default")
      (node (ref "U1") (pin "Y8") (pinfunction "IO_L14N_T2_SRCC_13_Y8") (pintype "passive+no_connect"))
    )
    (net (code "268") (name "unconnected-(U1D-IO_L14P_T2_SRCC_13-PadY9)") (class "Default")
      (node (ref "U1") (pin "Y9") (pinfunction "IO_L14P_T2_SRCC_13_Y9") (pintype "passive+no_connect"))
    )
    (net (code "269") (name "unconnected-(U1D-IO_L15N_T2_DQS_13-PadW8)") (class "Default")
      (node (ref "U1") (pin "W8") (pinfunction "IO_L15N_T2_DQS_13_W8") (pintype "passive+no_connect"))
    )
    (net (code "270") (name "unconnected-(U1D-IO_L15P_T2_DQS_13-PadV8)") (class "Default")
      (node (ref "U1") (pin "V8") (pinfunction "IO_L15P_T2_DQS_13_V8") (pintype "passive+no_connect"))
    )
    (net (code "271") (name "unconnected-(U1D-IO_L16N_T2_13-PadW9)") (class "Default")
      (node (ref "U1") (pin "W9") (pinfunction "IO_L16N_T2_13_W9") (pintype "passive+no_connect"))
    )
    (net (code "272") (name "unconnected-(U1D-IO_L16P_T2_13-PadW10)") (class "Default")
      (node (ref "U1") (pin "W10") (pinfunction "IO_L16P_T2_13_W10") (pintype "passive+no_connect"))
    )
    (net (code "273") (name "unconnected-(U1D-IO_L17N_T2_13-PadU8)") (class "Default")
      (node (ref "U1") (pin "U8") (pinfunction "IO_L17N_T2_13_U8") (pintype "passive+no_connect"))
    )
    (net (code "274") (name "unconnected-(U1D-IO_L17P_T2_13-PadU9)") (class "Default")
      (node (ref "U1") (pin "U9") (pinfunction "IO_L17P_T2_13_U9") (pintype "passive+no_connect"))
    )
    (net (code "275") (name "unconnected-(U1D-IO_L18N_T2_13-PadY11)") (class "Default")
      (node (ref "U1") (pin "Y11") (pinfunction "IO_L18N_T2_13_Y11") (pintype "passive+no_connect"))
    )
    (net (code "276") (name "unconnected-(U1D-IO_L18P_T2_13-PadW11)") (class "Default")
      (node (ref "U1") (pin "W11") (pinfunction "IO_L18P_T2_13_W11") (pintype "passive+no_connect"))
    )
    (net (code "277") (name "unconnected-(U1D-IO_L19N_T3_VREF_13-PadU5)") (class "Default")
      (node (ref "U1") (pin "U5") (pinfunction "IO_L19N_T3_VREF_13_U5") (pintype "passive+no_connect"))
    )
    (net (code "278") (name "unconnected-(U1D-IO_L19P_T3_13-PadT5)") (class "Default")
      (node (ref "U1") (pin "T5") (pinfunction "IO_L19P_T3_13_T5") (pintype "passive+no_connect"))
    )
    (net (code "279") (name "unconnected-(U1D-IO_L20N_T3_13-PadY13)") (class "Default")
      (node (ref "U1") (pin "Y13") (pinfunction "IO_L20N_T3_13_Y13") (pintype "passive+no_connect"))
    )
    (net (code "280") (name "unconnected-(U1D-IO_L20P_T3_13-PadY12)") (class "Default")
      (node (ref "U1") (pin "Y12") (pinfunction "IO_L20P_T3_13_Y12") (pintype "passive+no_connect"))
    )
    (net (code "281") (name "unconnected-(U1D-IO_L21N_T3_DQS_13-PadV10)") (class "Default")
      (node (ref "U1") (pin "V10") (pinfunction "IO_L21N_T3_DQS_13_V10") (pintype "passive+no_connect"))
    )
    (net (code "282") (name "unconnected-(U1D-IO_L21P_T3_DQS_13-PadV11)") (class "Default")
      (node (ref "U1") (pin "V11") (pinfunction "IO_L21P_T3_DQS_13_V11") (pintype "passive+no_connect"))
    )
    (net (code "283") (name "unconnected-(U1D-IO_L22N_T3_13-PadW6)") (class "Default")
      (node (ref "U1") (pin "W6") (pinfunction "IO_L22N_T3_13_W6") (pintype "passive+no_connect"))
    )
    (net (code "284") (name "unconnected-(U1D-IO_L22P_T3_13-PadV6)") (class "Default")
      (node (ref "U1") (pin "V6") (pinfunction "IO_L22P_T3_13_V6") (pintype "passive+no_connect"))
    )
    (net (code "285") (name "unconnected-(U1G-PS_DDR_DQS_P3_502-PadW5)") (class "Default")
      (node (ref "U1") (pin "W5") (pinfunction "PS_DDR_DQS_P3_502_W5") (pintype "passive"))
    )
  )
)
